# V1.net
KiCad netlist of a schematic drawn in EAGLE
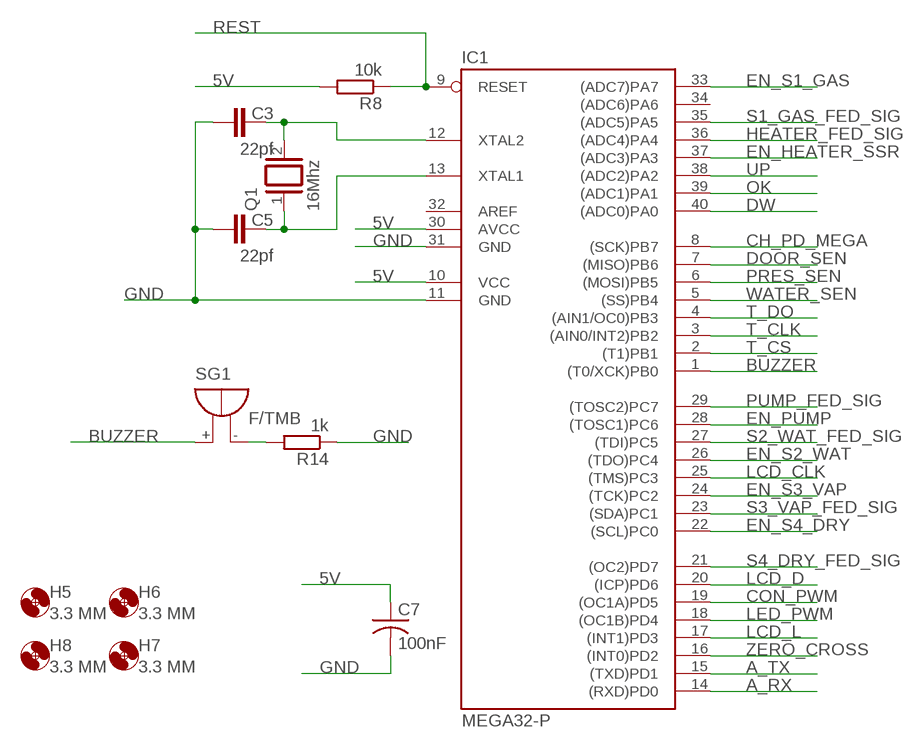
[diagram p0: schematic, sheet 1]
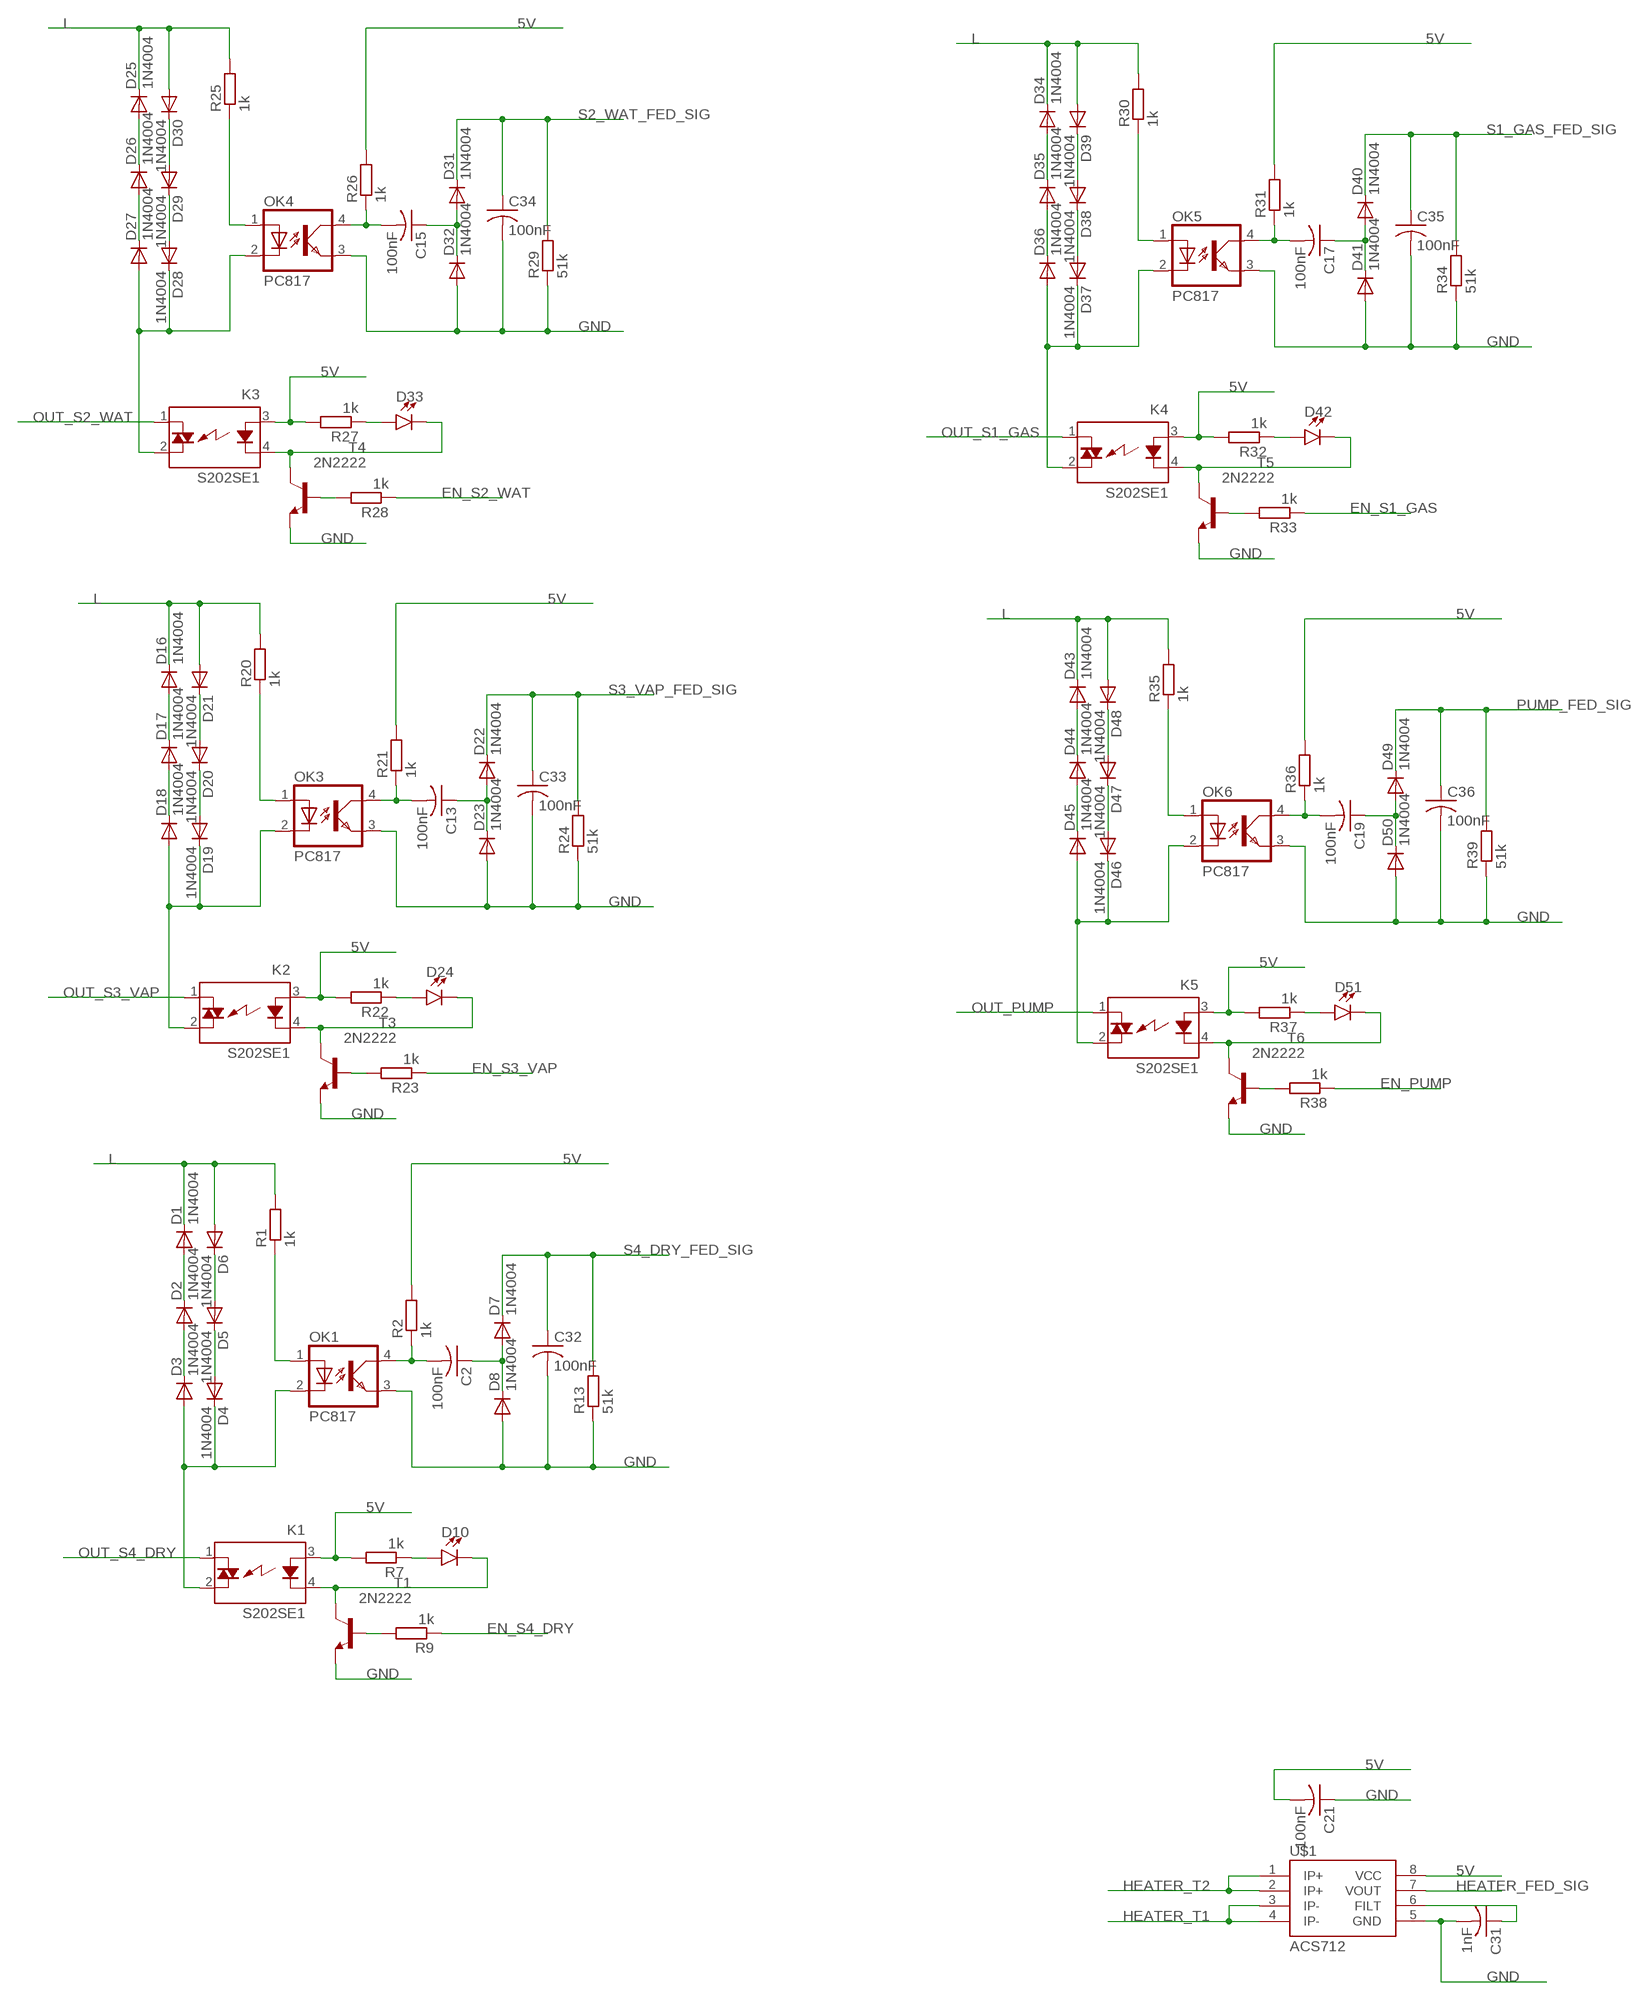
[diagram p1: schematic, sheet 2]
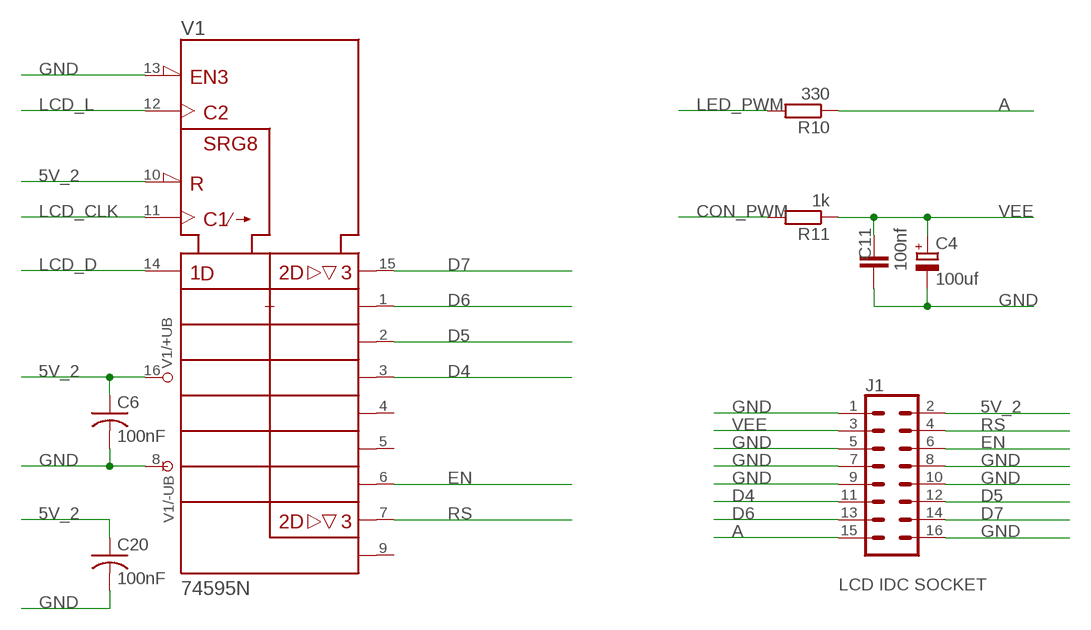
[diagram p2: schematic, sheet 3]
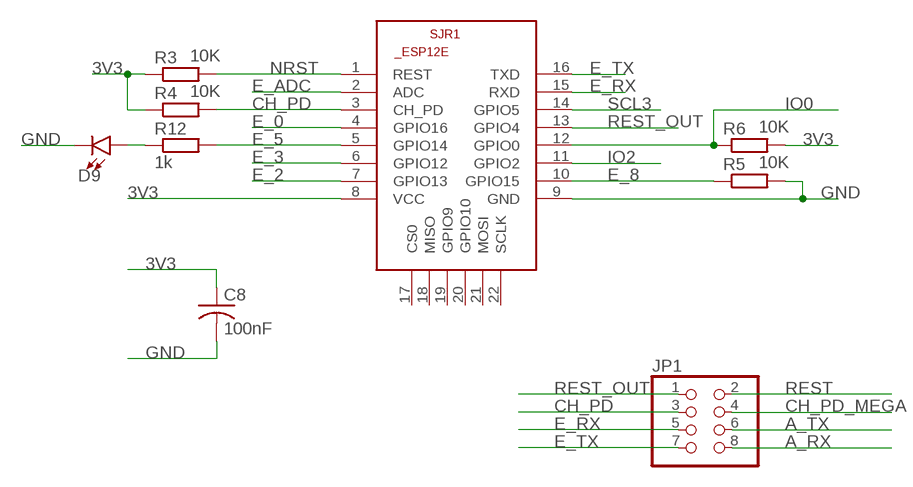
[diagram p3: schematic, sheet 4]
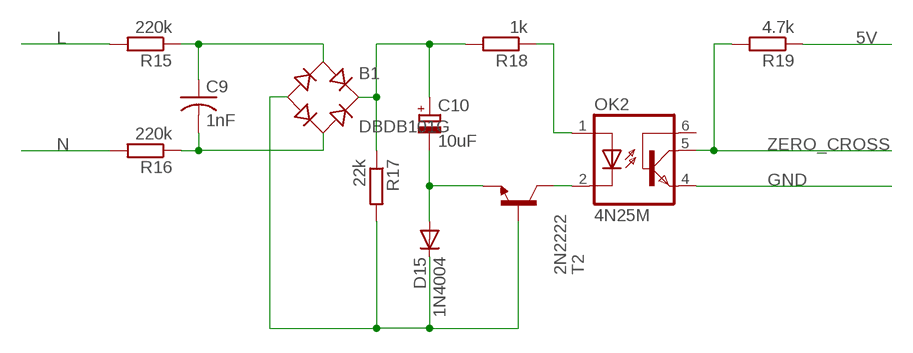
[diagram p4: schematic, sheet 5]
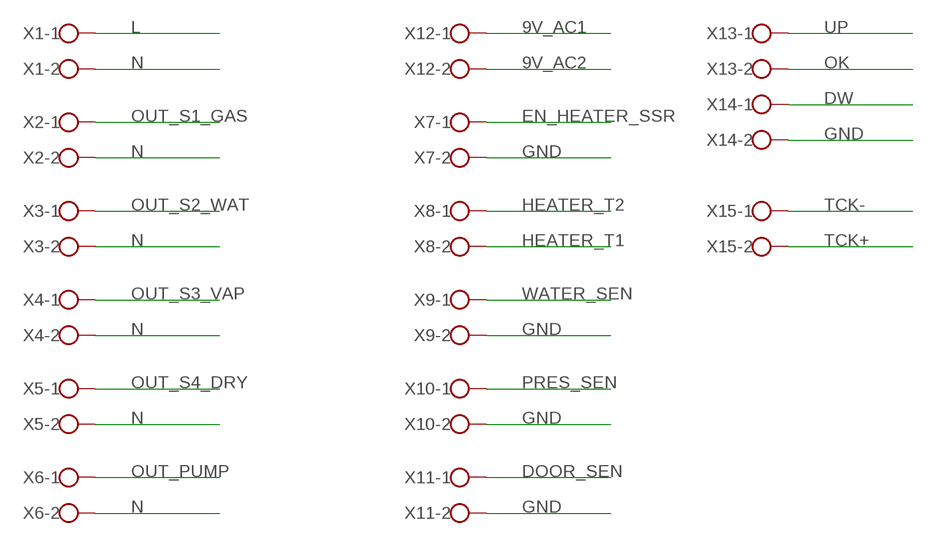
[diagram p5: schematic, sheet 6]
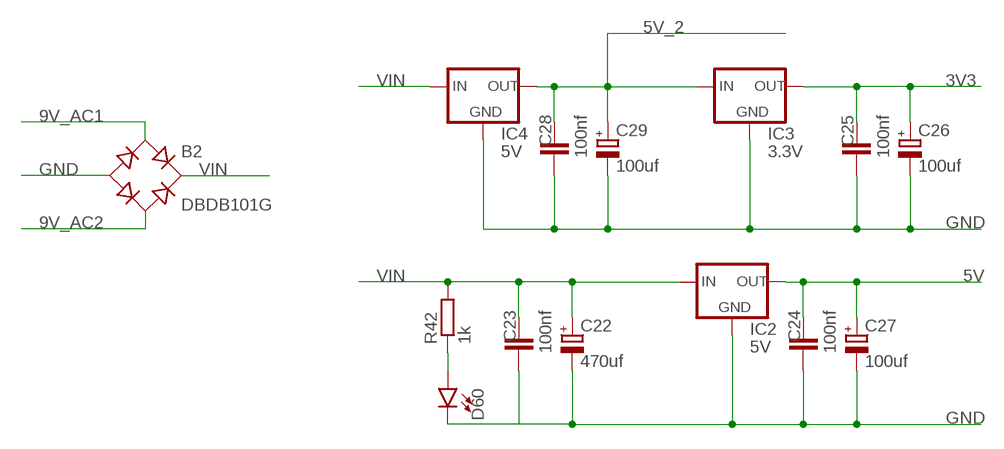
[diagram p6: schematic, sheet 7]
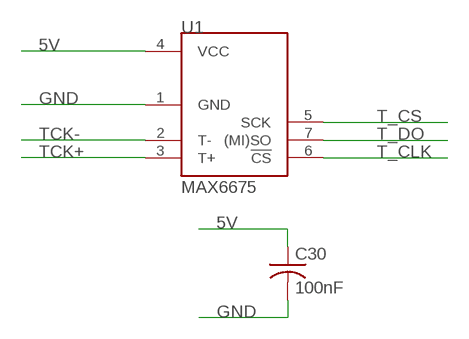
[diagram p7: schematic, sheet 8]

(export (version "E")
  (design (tool "Eeschema 10.0.6"))
  (components
    (comp (ref "C2")
      (value "100nF")
      (footprint "eagle-import:C050-035X075")
      (libsource (lib "eagle-import") (part "C-US050-035X075"))
    )
    (comp (ref "C13")
      (value "100nF")
      (footprint "eagle-import:C050-035X075")
      (libsource (lib "eagle-import") (part "C-US050-035X075"))
    )
    (comp (ref "C15")
      (value "100nF")
      (footprint "eagle-import:C050-035X075")
      (libsource (lib "eagle-import") (part "C-US050-035X075"))
    )
    (comp (ref "C17")
      (value "100nF")
      (footprint "eagle-import:C050-035X075")
      (libsource (lib "eagle-import") (part "C-US050-035X075"))
    )
    (comp (ref "C19")
      (value "100nF")
      (footprint "eagle-import:C050-035X075")
      (libsource (lib "eagle-import") (part "C-US050-035X075"))
    )
    (comp (ref "C21")
      (value "100nF")
      (footprint "eagle-import:C050-035X075")
      (libsource (lib "eagle-import") (part "C-US050-035X075"))
    )
    (comp (ref "C31")
      (value "1nF")
      (footprint "eagle-import:C050-035X075")
      (libsource (lib "eagle-import") (part "C-US050-035X075"))
    )
    (comp (ref "C32")
      (value "100nF")
      (footprint "eagle-import:C050-035X075")
      (libsource (lib "eagle-import") (part "C-US050-035X075"))
    )
    (comp (ref "C33")
      (value "100nF")
      (footprint "eagle-import:C050-035X075")
      (libsource (lib "eagle-import") (part "C-US050-035X075"))
    )
    (comp (ref "C34")
      (value "100nF")
      (footprint "eagle-import:C050-035X075")
      (libsource (lib "eagle-import") (part "C-US050-035X075"))
    )
    (comp (ref "C35")
      (value "100nF")
      (footprint "eagle-import:C050-035X075")
      (libsource (lib "eagle-import") (part "C-US050-035X075"))
    )
    (comp (ref "C36")
      (value "100nF")
      (footprint "eagle-import:C050-035X075")
      (libsource (lib "eagle-import") (part "C-US050-035X075"))
    )
    (comp (ref "D1")
      (value "1N4004")
      (footprint "eagle-import:DO41-10")
      (libsource (lib "eagle-import") (part "1N4004"))
    )
    (comp (ref "D2")
      (value "1N4004")
      (footprint "eagle-import:DO41-10")
      (libsource (lib "eagle-import") (part "1N4004"))
    )
    (comp (ref "D3")
      (value "1N4004")
      (footprint "eagle-import:DO41-10")
      (libsource (lib "eagle-import") (part "1N4004"))
    )
    (comp (ref "D4")
      (value "1N4004")
      (footprint "eagle-import:DO41-10")
      (libsource (lib "eagle-import") (part "1N4004"))
    )
    (comp (ref "D5")
      (value "1N4004")
      (footprint "eagle-import:DO41-10")
      (libsource (lib "eagle-import") (part "1N4004"))
    )
    (comp (ref "D6")
      (value "1N4004")
      (footprint "eagle-import:DO41-10")
      (libsource (lib "eagle-import") (part "1N4004"))
    )
    (comp (ref "D7")
      (value "1N4004")
      (footprint "eagle-import:DO41-10")
      (libsource (lib "eagle-import") (part "1N4004"))
    )
    (comp (ref "D8")
      (value "1N4004")
      (footprint "eagle-import:DO41-10")
      (libsource (lib "eagle-import") (part "1N4004"))
    )
    (comp (ref "D10")
      (value "LED5MM")
      (footprint "eagle-import:LED_5MM")
      (libsource (lib "eagle-import") (part "LED5MM"))
    )
    (comp (ref "D16")
      (value "1N4004")
      (footprint "eagle-import:DO41-10")
      (libsource (lib "eagle-import") (part "1N4004"))
    )
    (comp (ref "D17")
      (value "1N4004")
      (footprint "eagle-import:DO41-10")
      (libsource (lib "eagle-import") (part "1N4004"))
    )
    (comp (ref "D18")
      (value "1N4004")
      (footprint "eagle-import:DO41-10")
      (libsource (lib "eagle-import") (part "1N4004"))
    )
    (comp (ref "D19")
      (value "1N4004")
      (footprint "eagle-import:DO41-10")
      (libsource (lib "eagle-import") (part "1N4004"))
    )
    (comp (ref "D20")
      (value "1N4004")
      (footprint "eagle-import:DO41-10")
      (libsource (lib "eagle-import") (part "1N4004"))
    )
    (comp (ref "D21")
      (value "1N4004")
      (footprint "eagle-import:DO41-10")
      (libsource (lib "eagle-import") (part "1N4004"))
    )
    (comp (ref "D22")
      (value "1N4004")
      (footprint "eagle-import:DO41-10")
      (libsource (lib "eagle-import") (part "1N4004"))
    )
    (comp (ref "D23")
      (value "1N4004")
      (footprint "eagle-import:DO41-10")
      (libsource (lib "eagle-import") (part "1N4004"))
    )
    (comp (ref "D24")
      (value "LED5MM")
      (footprint "eagle-import:LED_5MM")
      (libsource (lib "eagle-import") (part "LED5MM"))
    )
    (comp (ref "D25")
      (value "1N4004")
      (footprint "eagle-import:DO41-10")
      (libsource (lib "eagle-import") (part "1N4004"))
    )
    (comp (ref "D26")
      (value "1N4004")
      (footprint "eagle-import:DO41-10")
      (libsource (lib "eagle-import") (part "1N4004"))
    )
    (comp (ref "D27")
      (value "1N4004")
      (footprint "eagle-import:DO41-10")
      (libsource (lib "eagle-import") (part "1N4004"))
    )
    (comp (ref "D28")
      (value "1N4004")
      (footprint "eagle-import:DO41-10")
      (libsource (lib "eagle-import") (part "1N4004"))
    )
    (comp (ref "D29")
      (value "1N4004")
      (footprint "eagle-import:DO41-10")
      (libsource (lib "eagle-import") (part "1N4004"))
    )
    (comp (ref "D30")
      (value "1N4004")
      (footprint "eagle-import:DO41-10")
      (libsource (lib "eagle-import") (part "1N4004"))
    )
    (comp (ref "D31")
      (value "1N4004")
      (footprint "eagle-import:DO41-10")
      (libsource (lib "eagle-import") (part "1N4004"))
    )
    (comp (ref "D32")
      (value "1N4004")
      (footprint "eagle-import:DO41-10")
      (libsource (lib "eagle-import") (part "1N4004"))
    )
    (comp (ref "D33")
      (value "LED5MM")
      (footprint "eagle-import:LED_5MM")
      (libsource (lib "eagle-import") (part "LED5MM"))
    )
    (comp (ref "D34")
      (value "1N4004")
      (footprint "eagle-import:DO41-10")
      (libsource (lib "eagle-import") (part "1N4004"))
    )
    (comp (ref "D35")
      (value "1N4004")
      (footprint "eagle-import:DO41-10")
      (libsource (lib "eagle-import") (part "1N4004"))
    )
    (comp (ref "D36")
      (value "1N4004")
      (footprint "eagle-import:DO41-10")
      (libsource (lib "eagle-import") (part "1N4004"))
    )
    (comp (ref "D37")
      (value "1N4004")
      (footprint "eagle-import:DO41-10")
      (libsource (lib "eagle-import") (part "1N4004"))
    )
    (comp (ref "D38")
      (value "1N4004")
      (footprint "eagle-import:DO41-10")
      (libsource (lib "eagle-import") (part "1N4004"))
    )
    (comp (ref "D39")
      (value "1N4004")
      (footprint "eagle-import:DO41-10")
      (libsource (lib "eagle-import") (part "1N4004"))
    )
    (comp (ref "D40")
      (value "1N4004")
      (footprint "eagle-import:DO41-10")
      (libsource (lib "eagle-import") (part "1N4004"))
    )
    (comp (ref "D41")
      (value "1N4004")
      (footprint "eagle-import:DO41-10")
      (libsource (lib "eagle-import") (part "1N4004"))
    )
    (comp (ref "D42")
      (value "LED5MM")
      (footprint "eagle-import:LED_5MM")
      (libsource (lib "eagle-import") (part "LED5MM"))
    )
    (comp (ref "D43")
      (value "1N4004")
      (footprint "eagle-import:DO41-10")
      (libsource (lib "eagle-import") (part "1N4004"))
    )
    (comp (ref "D44")
      (value "1N4004")
      (footprint "eagle-import:DO41-10")
      (libsource (lib "eagle-import") (part "1N4004"))
    )
    (comp (ref "D45")
      (value "1N4004")
      (footprint "eagle-import:DO41-10")
      (libsource (lib "eagle-import") (part "1N4004"))
    )
    (comp (ref "D46")
      (value "1N4004")
      (footprint "eagle-import:DO41-10")
      (libsource (lib "eagle-import") (part "1N4004"))
    )
    (comp (ref "D47")
      (value "1N4004")
      (footprint "eagle-import:DO41-10")
      (libsource (lib "eagle-import") (part "1N4004"))
    )
    (comp (ref "D48")
      (value "1N4004")
      (footprint "eagle-import:DO41-10")
      (libsource (lib "eagle-import") (part "1N4004"))
    )
    (comp (ref "D49")
      (value "1N4004")
      (footprint "eagle-import:DO41-10")
      (libsource (lib "eagle-import") (part "1N4004"))
    )
    (comp (ref "D50")
      (value "1N4004")
      (footprint "eagle-import:DO41-10")
      (libsource (lib "eagle-import") (part "1N4004"))
    )
    (comp (ref "D51")
      (value "LED5MM")
      (footprint "eagle-import:LED_5MM")
      (libsource (lib "eagle-import") (part "LED5MM"))
    )
    (comp (ref "K1")
      (value "S202SE1")
      (footprint "eagle-import:S2XXEX")
      (libsource (lib "eagle-import") (part "S202SE1"))
    )
    (comp (ref "K2")
      (value "S202SE1")
      (footprint "eagle-import:S2XXEX")
      (libsource (lib "eagle-import") (part "S202SE1"))
    )
    (comp (ref "K3")
      (value "S202SE1")
      (footprint "eagle-import:S2XXEX")
      (libsource (lib "eagle-import") (part "S202SE1"))
    )
    (comp (ref "K4")
      (value "S202SE1")
      (footprint "eagle-import:S2XXEX")
      (libsource (lib "eagle-import") (part "S202SE1"))
    )
    (comp (ref "K5")
      (value "S202SE1")
      (footprint "eagle-import:S2XXEX")
      (libsource (lib "eagle-import") (part "S202SE1"))
    )
    (comp (ref "OK1")
      (value "PC817")
      (footprint "eagle-import:DIL04")
      (libsource (lib "eagle-import") (part "PC817"))
    )
    (comp (ref "OK3")
      (value "PC817")
      (footprint "eagle-import:DIL04")
      (libsource (lib "eagle-import") (part "PC817"))
    )
    (comp (ref "OK4")
      (value "PC817")
      (footprint "eagle-import:DIL04")
      (libsource (lib "eagle-import") (part "PC817"))
    )
    (comp (ref "OK5")
      (value "PC817")
      (footprint "eagle-import:DIL04")
      (libsource (lib "eagle-import") (part "PC817"))
    )
    (comp (ref "OK6")
      (value "PC817")
      (footprint "eagle-import:DIL04")
      (libsource (lib "eagle-import") (part "PC817"))
    )
    (comp (ref "R1")
      (value "1k")
      (footprint "eagle-import:0207_10")
      (libsource (lib "eagle-import") (part "R-EU_0207/10"))
    )
    (comp (ref "R2")
      (value "1k")
      (footprint "eagle-import:0207_10")
      (libsource (lib "eagle-import") (part "R-EU_0207/10"))
    )
    (comp (ref "R7")
      (value "1k")
      (footprint "eagle-import:0207_10")
      (libsource (lib "eagle-import") (part "R-EU_0207/10"))
    )
    (comp (ref "R9")
      (value "1k")
      (footprint "eagle-import:0207_10")
      (libsource (lib "eagle-import") (part "R-EU_0207/10"))
    )
    (comp (ref "R13")
      (value "51k")
      (footprint "eagle-import:0207_10")
      (libsource (lib "eagle-import") (part "R-EU_0207/10"))
    )
    (comp (ref "R20")
      (value "1k")
      (footprint "eagle-import:0207_10")
      (libsource (lib "eagle-import") (part "R-EU_0207/10"))
    )
    (comp (ref "R21")
      (value "1k")
      (footprint "eagle-import:0207_10")
      (libsource (lib "eagle-import") (part "R-EU_0207/10"))
    )
    (comp (ref "R22")
      (value "1k")
      (footprint "eagle-import:0207_10")
      (libsource (lib "eagle-import") (part "R-EU_0207/10"))
    )
    (comp (ref "R23")
      (value "1k")
      (footprint "eagle-import:0207_10")
      (libsource (lib "eagle-import") (part "R-EU_0207/10"))
    )
    (comp (ref "R24")
      (value "51k")
      (footprint "eagle-import:0207_10")
      (libsource (lib "eagle-import") (part "R-EU_0207/10"))
    )
    (comp (ref "R25")
      (value "1k")
      (footprint "eagle-import:0207_10")
      (libsource (lib "eagle-import") (part "R-EU_0207/10"))
    )
    (comp (ref "R26")
      (value "1k")
      (footprint "eagle-import:0207_10")
      (libsource (lib "eagle-import") (part "R-EU_0207/10"))
    )
    (comp (ref "R27")
      (value "1k")
      (footprint "eagle-import:0207_10")
      (libsource (lib "eagle-import") (part "R-EU_0207/10"))
    )
    (comp (ref "R28")
      (value "1k")
      (footprint "eagle-import:0207_10")
      (libsource (lib "eagle-import") (part "R-EU_0207/10"))
    )
    (comp (ref "R29")
      (value "51k")
      (footprint "eagle-import:0207_10")
      (libsource (lib "eagle-import") (part "R-EU_0207/10"))
    )
    (comp (ref "R30")
      (value "1k")
      (footprint "eagle-import:0207_10")
      (libsource (lib "eagle-import") (part "R-EU_0207/10"))
    )
    (comp (ref "R31")
      (value "1k")
      (footprint "eagle-import:0207_10")
      (libsource (lib "eagle-import") (part "R-EU_0207/10"))
    )
    (comp (ref "R32")
      (value "1k")
      (footprint "eagle-import:0207_10")
      (libsource (lib "eagle-import") (part "R-EU_0207/10"))
    )
    (comp (ref "R33")
      (value "1k")
      (footprint "eagle-import:0207_10")
      (libsource (lib "eagle-import") (part "R-EU_0207/10"))
    )
    (comp (ref "R34")
      (value "51k")
      (footprint "eagle-import:0207_10")
      (libsource (lib "eagle-import") (part "R-EU_0207/10"))
    )
    (comp (ref "R35")
      (value "1k")
      (footprint "eagle-import:0207_10")
      (libsource (lib "eagle-import") (part "R-EU_0207/10"))
    )
    (comp (ref "R36")
      (value "1k")
      (footprint "eagle-import:0207_10")
      (libsource (lib "eagle-import") (part "R-EU_0207/10"))
    )
    (comp (ref "R37")
      (value "1k")
      (footprint "eagle-import:0207_10")
      (libsource (lib "eagle-import") (part "R-EU_0207/10"))
    )
    (comp (ref "R38")
      (value "1k")
      (footprint "eagle-import:0207_10")
      (libsource (lib "eagle-import") (part "R-EU_0207/10"))
    )
    (comp (ref "R39")
      (value "51k")
      (footprint "eagle-import:0207_10")
      (libsource (lib "eagle-import") (part "R-EU_0207/10"))
    )
    (comp (ref "T1")
      (value "2N2222")
      (footprint "eagle-import:TO92-EBC-OVAL")
      (libsource (lib "eagle-import") (part "2N2222"))
    )
    (comp (ref "T3")
      (value "2N2222")
      (footprint "eagle-import:TO92-EBC-OVAL")
      (libsource (lib "eagle-import") (part "2N2222"))
    )
    (comp (ref "T4")
      (value "2N2222")
      (footprint "eagle-import:TO92-EBC-OVAL")
      (libsource (lib "eagle-import") (part "2N2222"))
    )
    (comp (ref "T5")
      (value "2N2222")
      (footprint "eagle-import:TO92-EBC-OVAL")
      (libsource (lib "eagle-import") (part "2N2222"))
    )
    (comp (ref "T6")
      (value "2N2222")
      (footprint "eagle-import:TO92-EBC-OVAL")
      (libsource (lib "eagle-import") (part "2N2222"))
    )
    (comp (ref "U$1")
      (value "ACS712")
      (footprint "eagle-import:SO08")
      (libsource (lib "eagle-import") (part "ACS712"))
    )
    (comp (ref "X1")
      (value "W237-102")
      (footprint "eagle-import:W237-102")
      (fields (field (name "MPN") "237-102"))
      (libsource (lib "eagle-import") (part "W237-102"))
    )
    (comp (ref "X2")
      (value "W237-102")
      (footprint "eagle-import:W237-102")
      (fields (field (name "MPN") "237-102"))
      (libsource (lib "eagle-import") (part "W237-102"))
    )
    (comp (ref "X3")
      (value "W237-102")
      (footprint "eagle-import:W237-102")
      (fields (field (name "MPN") "237-102"))
      (libsource (lib "eagle-import") (part "W237-102"))
    )
    (comp (ref "X4")
      (value "W237-102")
      (footprint "eagle-import:W237-102")
      (fields (field (name "MPN") "237-102"))
      (libsource (lib "eagle-import") (part "W237-102"))
    )
    (comp (ref "X5")
      (value "W237-102")
      (footprint "eagle-import:W237-102")
      (fields (field (name "MPN") "237-102"))
      (libsource (lib "eagle-import") (part "W237-102"))
    )
    (comp (ref "X6")
      (value "W237-102")
      (footprint "eagle-import:W237-102")
      (fields (field (name "MPN") "237-102"))
      (libsource (lib "eagle-import") (part "W237-102"))
    )
    (comp (ref "X7")
      (value "W237-102")
      (footprint "eagle-import:W237-102")
      (fields (field (name "MPN") "237-102"))
      (libsource (lib "eagle-import") (part "W237-102"))
    )
    (comp (ref "X8")
      (value "W237-102")
      (footprint "eagle-import:W237-102")
      (fields (field (name "MPN") "237-102"))
      (libsource (lib "eagle-import") (part "W237-102"))
    )
    (comp (ref "X9")
      (value "W237-102")
      (footprint "eagle-import:W237-102")
      (fields (field (name "MPN") "237-102"))
      (libsource (lib "eagle-import") (part "W237-102"))
    )
    (comp (ref "X10")
      (value "W237-102")
      (footprint "eagle-import:W237-102")
      (fields (field (name "MPN") "237-102"))
      (libsource (lib "eagle-import") (part "W237-102"))
    )
    (comp (ref "X11")
      (value "W237-102")
      (footprint "eagle-import:W237-102")
      (fields (field (name "MPN") "237-102"))
      (libsource (lib "eagle-import") (part "W237-102"))
    )
    (comp (ref "X12")
      (value "W237-102")
      (footprint "eagle-import:W237-102")
      (fields (field (name "MPN") "237-102"))
      (libsource (lib "eagle-import") (part "W237-102"))
    )
    (comp (ref "X13")
      (value "W237-102")
      (footprint "eagle-import:W237-102")
      (fields (field (name "MPN") "237-102"))
      (libsource (lib "eagle-import") (part "W237-102"))
    )
    (comp (ref "X14")
      (value "W237-102")
      (footprint "eagle-import:W237-102")
      (fields (field (name "MPN") "237-102"))
      (libsource (lib "eagle-import") (part "W237-102"))
    )
    (comp (ref "X15")
      (value "W237-102")
      (footprint "eagle-import:W237-102")
      (fields (field (name "MPN") "237-102"))
      (libsource (lib "eagle-import") (part "W237-102"))
    )
    (comp (ref "C3")
      (value "22pf")
      (footprint "eagle-import:C050-030X075")
      (libsource (lib "eagle-import") (part "C-EU050-030X075"))
    )
    (comp (ref "C5")
      (value "22pf")
      (footprint "eagle-import:C050-030X075")
      (libsource (lib "eagle-import") (part "C-EU050-030X075"))
    )
    (comp (ref "C7")
      (value "100nF")
      (footprint "eagle-import:C050-035X075")
      (libsource (lib "eagle-import") (part "C-US050-035X075"))
    )
    (comp (ref "H5")
      (value "3.3 MM")
      (footprint "eagle-import:3,3")
      (libsource (lib "eagle-import") (part "MOUNT-HOLE3.3"))
    )
    (comp (ref "H6")
      (value "3.3 MM")
      (footprint "eagle-import:3,3")
      (libsource (lib "eagle-import") (part "MOUNT-HOLE3.3"))
    )
    (comp (ref "H7")
      (value "3.3 MM")
      (footprint "eagle-import:3,3")
      (libsource (lib "eagle-import") (part "MOUNT-HOLE3.3"))
    )
    (comp (ref "H8")
      (value "3.3 MM")
      (footprint "eagle-import:3,3")
      (libsource (lib "eagle-import") (part "MOUNT-HOLE3.3"))
    )
    (comp (ref "IC1")
      (value "MEGA32-P")
      (footprint "eagle-import:DIL40")
      (fields (field (name "MPN") "ATMEGA32-16PU"))
      (libsource (lib "eagle-import") (part "MEGA32-P"))
    )
    (comp (ref "Q1")
      (value "16Mhz")
      (footprint "eagle-import:QS")
      (libsource (lib "eagle-import") (part "XTAL/S"))
    )
    (comp (ref "R8")
      (value "10k")
      (footprint "eagle-import:0207_10")
      (libsource (lib "eagle-import") (part "R-EU_0207/10"))
    )
    (comp (ref "R14")
      (value "1k")
      (footprint "eagle-import:0207_10")
      (libsource (lib "eagle-import") (part "R-EU_0207/10"))
    )
    (comp (ref "SG1")
      (value "F/TMB")
      (footprint "eagle-import:F_TMB")
      (libsource (lib "eagle-import") (part "F/TMB"))
    )
    (comp (ref "C4")
      (value "100uf")
      (footprint "eagle-import:E3,5-8")
      (libsource (lib "eagle-import") (part "CPOL-EUE3.5-8"))
    )
    (comp (ref "C6")
      (value "100nF")
      (footprint "eagle-import:C050-035X075")
      (libsource (lib "eagle-import") (part "C-US050-035X075"))
    )
    (comp (ref "C11")
      (value "100nf")
      (footprint "eagle-import:C050-030X075")
      (libsource (lib "eagle-import") (part "C-EU050-030X075"))
    )
    (comp (ref "C20")
      (value "100nF")
      (footprint "eagle-import:C050-035X075")
      (libsource (lib "eagle-import") (part "C-US050-035X075"))
    )
    (comp (ref "J1")
      (value "CONN_08X2")
      (footprint "eagle-import:2X8")
      (libsource (lib "eagle-import") (part "CONN_08X2"))
    )
    (comp (ref "R10")
      (value "330")
      (footprint "eagle-import:0207_10")
      (libsource (lib "eagle-import") (part "R-EU_0207/10"))
    )
    (comp (ref "R11")
      (value "1k")
      (footprint "eagle-import:0207_10")
      (libsource (lib "eagle-import") (part "R-EU_0207/10"))
    )
    (comp (ref "V1")
      (value "74595N")
      (footprint "eagle-import:DIL16")
      (libsource (lib "eagle-import") (part "74595N"))
    )
    (comp (ref "B2")
      (value "DBDB101G")
      (footprint "eagle-import:DB")
      (libsource (lib "eagle-import") (part "DB?GDB101"))
    )
    (comp (ref "C22")
      (value "470uf")
      (footprint "eagle-import:E3,5-8")
      (libsource (lib "eagle-import") (part "CPOL-EUE3.5-8"))
    )
    (comp (ref "C23")
      (value "100nf")
      (footprint "eagle-import:C050-030X075")
      (libsource (lib "eagle-import") (part "C-EU050-030X075"))
    )
    (comp (ref "C24")
      (value "100nf")
      (footprint "eagle-import:C050-030X075")
      (libsource (lib "eagle-import") (part "C-EU050-030X075"))
    )
    (comp (ref "C25")
      (value "100nf")
      (footprint "eagle-import:C050-030X075")
      (libsource (lib "eagle-import") (part "C-EU050-030X075"))
    )
    (comp (ref "C26")
      (value "100uf")
      (footprint "eagle-import:E3,5-8")
      (libsource (lib "eagle-import") (part "CPOL-EUE3.5-8"))
    )
    (comp (ref "C27")
      (value "100uf")
      (footprint "eagle-import:E3,5-8")
      (libsource (lib "eagle-import") (part "CPOL-EUE3.5-8"))
    )
    (comp (ref "C28")
      (value "100nf")
      (footprint "eagle-import:C050-030X075")
      (libsource (lib "eagle-import") (part "C-EU050-030X075"))
    )
    (comp (ref "C29")
      (value "100uf")
      (footprint "eagle-import:E3,5-8")
      (libsource (lib "eagle-import") (part "CPOL-EUE3.5-8"))
    )
    (comp (ref "D60")
      (value "LED5MM")
      (footprint "eagle-import:LED_5MM")
      (libsource (lib "eagle-import") (part "LED5MM"))
    )
    (comp (ref "IC2")
      (value "5V")
      (footprint "eagle-import:78XXL")
      (libsource (lib "eagle-import") (part "V_REG_78XXSIDE"))
    )
    (comp (ref "IC3")
      (value "3.3V")
      (footprint "eagle-import:78XXL")
      (libsource (lib "eagle-import") (part "V_REG_78XXSIDE"))
    )
    (comp (ref "IC4")
      (value "5V")
      (footprint "eagle-import:78XXL")
      (libsource (lib "eagle-import") (part "V_REG_78XXSIDE"))
    )
    (comp (ref "R42")
      (value "1k")
      (footprint "eagle-import:0207_10")
      (libsource (lib "eagle-import") (part "R-EU_0207/10"))
    )
    (comp (ref "C8")
      (value "100nF")
      (footprint "eagle-import:C050-035X075")
      (libsource (lib "eagle-import") (part "C-US050-035X075"))
    )
    (comp (ref "D9")
      (value "LED5MM")
      (footprint "eagle-import:LED_5MM")
      (libsource (lib "eagle-import") (part "LED5MM"))
    )
    (comp (ref "JP1")
      (value "PINHD-2X4")
      (footprint "eagle-import:2X04")
      (libsource (lib "eagle-import") (part "PINHD-2X4"))
    )
    (comp (ref "R3")
      (value "10K")
      (footprint "eagle-import:0207_10")
      (libsource (lib "eagle-import") (part "rcl_334_R-EU_0207/10"))
    )
    (comp (ref "R4")
      (value "10K")
      (footprint "eagle-import:0207_10")
      (libsource (lib "eagle-import") (part "rcl_334_R-EU_0207/10"))
    )
    (comp (ref "R5")
      (value "10K")
      (footprint "eagle-import:0207_10")
      (libsource (lib "eagle-import") (part "rcl_334_R-EU_0207/10"))
    )
    (comp (ref "R6")
      (value "10K")
      (footprint "eagle-import:0207_10")
      (libsource (lib "eagle-import") (part "rcl_334_R-EU_0207/10"))
    )
    (comp (ref "R12")
      (value "1k")
      (footprint "eagle-import:0207_10")
      (libsource (lib "eagle-import") (part "R-EU_0207/10"))
    )
    (comp (ref "SJR1")
      (value "ESP8266-12EESP12E")
      (footprint "eagle-import:ESP8266-ESP12E")
      (libsource (lib "eagle-import") (part "ESP8266-12EESP12E"))
    )
    (comp (ref "B1")
      (value "DBDB101G")
      (footprint "eagle-import:DB")
      (libsource (lib "eagle-import") (part "DB?GDB101"))
    )
    (comp (ref "C9")
      (value "1nF")
      (footprint "eagle-import:C050-035X075")
      (libsource (lib "eagle-import") (part "C-US050-035X075"))
    )
    (comp (ref "C10")
      (value "10uF")
      (footprint "eagle-import:E2,5-7")
      (libsource (lib "eagle-import") (part "rcl_334_CPOL-EUE2.5-7"))
    )
    (comp (ref "D15")
      (value "1N4004")
      (footprint "eagle-import:DO41-10")
      (libsource (lib "eagle-import") (part "1N4004"))
    )
    (comp (ref "OK2")
      (value "4N25M")
      (footprint "eagle-import:DIL06")
      (fields (field (name "MPN") "4N25-M"))
      (libsource (lib "eagle-import") (part "4N?M25"))
    )
    (comp (ref "R15")
      (value "220k")
      (footprint "eagle-import:0207_10")
      (libsource (lib "eagle-import") (part "R-EU_0207/10"))
    )
    (comp (ref "R16")
      (value "220k")
      (footprint "eagle-import:0207_10")
      (libsource (lib "eagle-import") (part "R-EU_0207/10"))
    )
    (comp (ref "R17")
      (value "22k")
      (footprint "eagle-import:0207_10")
      (libsource (lib "eagle-import") (part "R-EU_0207/10"))
    )
    (comp (ref "R18")
      (value "1k")
      (footprint "eagle-import:0207_10")
      (libsource (lib "eagle-import") (part "R-EU_0207/10"))
    )
    (comp (ref "R19")
      (value "4.7k")
      (footprint "eagle-import:0207_10")
      (libsource (lib "eagle-import") (part "R-EU_0207/10"))
    )
    (comp (ref "T2")
      (value "2N2222")
      (footprint "eagle-import:TO92-EBC-OVAL")
      (libsource (lib "eagle-import") (part "2N2222"))
    )
    (comp (ref "C30")
      (value "100nF")
      (footprint "eagle-import:C050-035X075")
      (libsource (lib "eagle-import") (part "C-US050-035X075"))
    )
    (comp (ref "U1")
      (value "MAX6675")
      (footprint "eagle-import:SOIC8")
      (libsource (lib "eagle-import") (part "MAX6675"))
    )
  )
  (nets
    (net (code "1") (name "3V3") (class "Default")
      (node (ref "C25") (pin "2") (pinfunction "2_2") (pintype "passive"))
      (node (ref "C26") (pin "+") (pinfunction "+_+") (pintype "passive"))
      (node (ref "C8") (pin "1") (pinfunction "1_1") (pintype "passive"))
      (node (ref "IC3") (pin "OUT") (pinfunction "OUT_OUT") (pintype "output"))
      (node (ref "R3") (pin "1") (pinfunction "1_1") (pintype "passive"))
      (node (ref "R4") (pin "1") (pinfunction "1_1") (pintype "passive"))
      (node (ref "R6") (pin "2") (pinfunction "2_2") (pintype "passive"))
      (node (ref "SJR1") (pin "8") (pinfunction "VCC_8") (pintype "bidirectional"))
    )
    (net (code "2") (name "5V") (class "Default")
      (node (ref "C21") (pin "2") (pinfunction "2_2") (pintype "passive"))
      (node (ref "C24") (pin "2") (pinfunction "2_2") (pintype "passive"))
      (node (ref "C27") (pin "+") (pinfunction "+_+") (pintype "passive"))
      (node (ref "C30") (pin "1") (pinfunction "1_1") (pintype "passive"))
      (node (ref "C7") (pin "1") (pinfunction "1_1") (pintype "passive"))
      (node (ref "IC1") (pin "10") (pinfunction "VCC_10") (pintype "power_in"))
      (node (ref "IC1") (pin "30") (pinfunction "AVCC_30") (pintype "power_in"))
      (node (ref "IC2") (pin "OUT") (pinfunction "OUT_OUT") (pintype "output"))
      (node (ref "K1") (pin "3") (pinfunction "A_3") (pintype "passive"))
      (node (ref "K2") (pin "3") (pinfunction "A_3") (pintype "passive"))
      (node (ref "K3") (pin "3") (pinfunction "A_3") (pintype "passive"))
      (node (ref "K4") (pin "3") (pinfunction "A_3") (pintype "passive"))
      (node (ref "K5") (pin "3") (pinfunction "A_3") (pintype "passive"))
      (node (ref "R19") (pin "1") (pinfunction "1_1") (pintype "passive"))
      (node (ref "R2") (pin "2") (pinfunction "2_2") (pintype "passive"))
      (node (ref "R21") (pin "2") (pinfunction "2_2") (pintype "passive"))
      (node (ref "R22") (pin "2") (pinfunction "2_2") (pintype "passive"))
      (node (ref "R26") (pin "2") (pinfunction "2_2") (pintype "passive"))
      (node (ref "R27") (pin "2") (pinfunction "2_2") (pintype "passive"))
      (node (ref "R31") (pin "2") (pinfunction "2_2") (pintype "passive"))
      (node (ref "R32") (pin "2") (pinfunction "2_2") (pintype "passive"))
      (node (ref "R36") (pin "2") (pinfunction "2_2") (pintype "passive"))
      (node (ref "R37") (pin "2") (pinfunction "2_2") (pintype "passive"))
      (node (ref "R7") (pin "2") (pinfunction "2_2") (pintype "passive"))
      (node (ref "R8") (pin "2") (pinfunction "2_2") (pintype "passive"))
      (node (ref "U$1") (pin "8") (pinfunction "VCC_8") (pintype "bidirectional"))
      (node (ref "U1") (pin "4") (pinfunction "VCC_4") (pintype "bidirectional"))
    )
    (net (code "3") (name "5V_2") (class "Default")
      (node (ref "C20") (pin "1") (pinfunction "1_1") (pintype "passive"))
      (node (ref "C28") (pin "2") (pinfunction "2_2") (pintype "passive"))
      (node (ref "C29") (pin "+") (pinfunction "+_+") (pintype "passive"))
      (node (ref "C6") (pin "1") (pinfunction "1_1") (pintype "passive"))
      (node (ref "IC3") (pin "IN") (pinfunction "IN_IN") (pintype "input"))
      (node (ref "IC4") (pin "OUT") (pinfunction "OUT_OUT") (pintype "output"))
      (node (ref "J1") (pin "2") (pinfunction "2_2") (pintype "passive"))
      (node (ref "V1") (pin "10") (pinfunction "~{SRCLR}_10") (pintype "input"))
      (node (ref "V1") (pin "16") (pinfunction "+UB_16") (pintype "power_in"))
    )
    (net (code "4") (name "9V_AC1") (class "Default")
      (node (ref "B2") (pin "AC1") (pinfunction "AC1_AC1") (pintype "passive"))
      (node (ref "X12") (pin "1") (pinfunction "KL_1") (pintype "passive"))
    )
    (net (code "5") (name "9V_AC2") (class "Default")
      (node (ref "B2") (pin "AC2") (pinfunction "AC2_AC2") (pintype "passive"))
      (node (ref "X12") (pin "2") (pinfunction "KL_2") (pintype "passive"))
    )
    (net (code "6") (name "A") (class "Default")
      (node (ref "J1") (pin "15") (pinfunction "15_15") (pintype "passive"))
      (node (ref "R10") (pin "1") (pinfunction "1_1") (pintype "passive"))
    )
    (net (code "7") (name "A_RX") (class "Default")
      (node (ref "IC1") (pin "14") (pinfunction "(RXD)PD0_14") (pintype "bidirectional"))
      (node (ref "JP1") (pin "8") (pinfunction "8_8") (pintype "passive"))
    )
    (net (code "8") (name "A_TX") (class "Default")
      (node (ref "IC1") (pin "15") (pinfunction "(TXD)PD1_15") (pintype "bidirectional"))
      (node (ref "JP1") (pin "6") (pinfunction "6_6") (pintype "passive"))
    )
    (net (code "9") (name "BUZZER") (class "Default")
      (node (ref "IC1") (pin "1") (pinfunction "(T0/XCK)PB0_1") (pintype "bidirectional"))
      (node (ref "SG1") (pin "+") (pinfunction "+_+") (pintype "passive"))
    )
    (net (code "10") (name "CH_PD") (class "Default")
      (node (ref "JP1") (pin "3") (pinfunction "3_3") (pintype "passive"))
      (node (ref "R4") (pin "2") (pinfunction "2_2") (pintype "passive"))
      (node (ref "SJR1") (pin "3") (pinfunction "CH_PD_3") (pintype "bidirectional"))
    )
    (net (code "11") (name "CH_PD_MEGA") (class "Default")
      (node (ref "IC1") (pin "8") (pinfunction "(SCK)PB7_8") (pintype "bidirectional"))
      (node (ref "JP1") (pin "4") (pinfunction "4_4") (pintype "passive"))
    )
    (net (code "12") (name "CON_PWM") (class "Default")
      (node (ref "IC1") (pin "19") (pinfunction "(OC1A)PD5_19") (pintype "bidirectional"))
      (node (ref "R11") (pin "2") (pinfunction "2_2") (pintype "passive"))
    )
    (net (code "13") (name "D4") (class "Default")
      (node (ref "J1") (pin "11") (pinfunction "11_11") (pintype "passive"))
      (node (ref "V1") (pin "3") (pinfunction "QD_3") (pintype "tri_state"))
    )
    (net (code "14") (name "D5") (class "Default")
      (node (ref "J1") (pin "12") (pinfunction "12_12") (pintype "passive"))
      (node (ref "V1") (pin "2") (pinfunction "QC_2") (pintype "tri_state"))
    )
    (net (code "15") (name "D6") (class "Default")
      (node (ref "J1") (pin "13") (pinfunction "13_13") (pintype "passive"))
      (node (ref "V1") (pin "1") (pinfunction "QB_1") (pintype "tri_state"))
    )
    (net (code "16") (name "D7") (class "Default")
      (node (ref "J1") (pin "14") (pinfunction "14_14") (pintype "passive"))
      (node (ref "V1") (pin "15") (pinfunction "QA_15") (pintype "tri_state"))
    )
    (net (code "17") (name "DOOR_SEN") (class "Default")
      (node (ref "IC1") (pin "7") (pinfunction "(MISO)PB6_7") (pintype "bidirectional"))
      (node (ref "X11") (pin "1") (pinfunction "KL_1") (pintype "passive"))
    )
    (net (code "18") (name "DW") (class "Default")
      (node (ref "IC1") (pin "40") (pinfunction "(ADC0)PA0_40") (pintype "bidirectional"))
      (node (ref "X14") (pin "1") (pinfunction "KL_1") (pintype "passive"))
    )
    (net (code "19") (name "EN") (class "Default")
      (node (ref "J1") (pin "6") (pinfunction "6_6") (pintype "passive"))
      (node (ref "V1") (pin "6") (pinfunction "QG_6") (pintype "tri_state"))
    )
    (net (code "20") (name "EN_HEATER_SSR") (class "Default")
      (node (ref "IC1") (pin "37") (pinfunction "(ADC3)PA3_37") (pintype "bidirectional"))
      (node (ref "X7") (pin "1") (pinfunction "KL_1") (pintype "passive"))
    )
    (net (code "21") (name "EN_PUMP") (class "Default")
      (node (ref "IC1") (pin "28") (pinfunction "(TOSC1)PC6_28") (pintype "bidirectional"))
      (node (ref "R38") (pin "1") (pinfunction "1_1") (pintype "passive"))
    )
    (net (code "22") (name "EN_S1_GAS") (class "Default")
      (node (ref "IC1") (pin "33") (pinfunction "(ADC7)PA7_33") (pintype "bidirectional"))
      (node (ref "R33") (pin "1") (pinfunction "1_1") (pintype "passive"))
    )
    (net (code "23") (name "EN_S2_WAT") (class "Default")
      (node (ref "IC1") (pin "26") (pinfunction "(TDO)PC4_26") (pintype "bidirectional"))
      (node (ref "R28") (pin "1") (pinfunction "1_1") (pintype "passive"))
    )
    (net (code "24") (name "EN_S3_VAP") (class "Default")
      (node (ref "IC1") (pin "24") (pinfunction "(TCK)PC2_24") (pintype "bidirectional"))
      (node (ref "R23") (pin "1") (pinfunction "1_1") (pintype "passive"))
    )
    (net (code "25") (name "EN_S4_DRY") (class "Default")
      (node (ref "IC1") (pin "22") (pinfunction "(SCL)PC0_22") (pintype "bidirectional"))
      (node (ref "R9") (pin "1") (pinfunction "1_1") (pintype "passive"))
    )
    (net (code "26") (name "E_0") (class "Default")
      (node (ref "SJR1") (pin "4") (pinfunction "GPIO16_4") (pintype "bidirectional"))
    )
    (net (code "27") (name "E_2") (class "Default")
      (node (ref "SJR1") (pin "7") (pinfunction "GPIO13_7") (pintype "bidirectional"))
    )
    (net (code "28") (name "E_3") (class "Default")
      (node (ref "SJR1") (pin "6") (pinfunction "GPIO12_6") (pintype "bidirectional"))
    )
    (net (code "29") (name "E_5") (class "Default")
      (node (ref "R12") (pin "2") (pinfunction "2_2") (pintype "passive"))
      (node (ref "SJR1") (pin "5") (pinfunction "GPIO14_5") (pintype "bidirectional"))
    )
    (net (code "30") (name "E_8") (class "Default")
      (node (ref "R5") (pin "1") (pinfunction "1_1") (pintype "passive"))
      (node (ref "SJR1") (pin "10") (pinfunction "GPIO15_10") (pintype "bidirectional"))
    )
    (net (code "31") (name "E_ADC") (class "Default")
      (node (ref "SJR1") (pin "2") (pinfunction "ADC_2") (pintype "bidirectional"))
    )
    (net (code "32") (name "E_RX") (class "Default")
      (node (ref "JP1") (pin "5") (pinfunction "5_5") (pintype "passive"))
      (node (ref "SJR1") (pin "15") (pinfunction "RXD_15") (pintype "bidirectional"))
    )
    (net (code "33") (name "E_TX") (class "Default")
      (node (ref "JP1") (pin "7") (pinfunction "7_7") (pintype "passive"))
      (node (ref "SJR1") (pin "16") (pinfunction "TXD_16") (pintype "bidirectional"))
    )
    (net (code "34") (name "GND") (class "Default")
      (node (ref "B2") (pin "-") (pinfunction "-_-") (pintype "passive"))
      (node (ref "C11") (pin "1") (pinfunction "1_1") (pintype "passive"))
      (node (ref "C20") (pin "2") (pinfunction "2_2") (pintype "passive"))
      (node (ref "C21") (pin "1") (pinfunction "1_1") (pintype "passive"))
      (node (ref "C22") (pin "-") (pinfunction "-_-") (pintype "passive"))
      (node (ref "C23") (pin "1") (pinfunction "1_1") (pintype "passive"))
      (node (ref "C24") (pin "1") (pinfunction "1_1") (pintype "passive"))
      (node (ref "C25") (pin "1") (pinfunction "1_1") (pintype "passive"))
      (node (ref "C26") (pin "-") (pinfunction "-_-") (pintype "passive"))
      (node (ref "C27") (pin "-") (pinfunction "-_-") (pintype "passive"))
      (node (ref "C28") (pin "1") (pinfunction "1_1") (pintype "passive"))
      (node (ref "C29") (pin "-") (pinfunction "-_-") (pintype "passive"))
      (node (ref "C3") (pin "1") (pinfunction "1_1") (pintype "passive"))
      (node (ref "C30") (pin "2") (pinfunction "2_2") (pintype "passive"))
      (node (ref "C31") (pin "2") (pinfunction "2_2") (pintype "passive"))
      (node (ref "C32") (pin "2") (pinfunction "2_2") (pintype "passive"))
      (node (ref "C33") (pin "2") (pinfunction "2_2") (pintype "passive"))
      (node (ref "C34") (pin "2") (pinfunction "2_2") (pintype "passive"))
      (node (ref "C35") (pin "2") (pinfunction "2_2") (pintype "passive"))
      (node (ref "C36") (pin "2") (pinfunction "2_2") (pintype "passive"))
      (node (ref "C4") (pin "-") (pinfunction "-_-") (pintype "passive"))
      (node (ref "C5") (pin "1") (pinfunction "1_1") (pintype "passive"))
      (node (ref "C6") (pin "2") (pinfunction "2_2") (pintype "passive"))
      (node (ref "C7") (pin "2") (pinfunction "2_2") (pintype "passive"))
      (node (ref "C8") (pin "2") (pinfunction "2_2") (pintype "passive"))
      (node (ref "D23") (pin "A") (pinfunction "A_A") (pintype "passive"))
      (node (ref "D32") (pin "A") (pinfunction "A_A") (pintype "passive"))
      (node (ref "D41") (pin "A") (pinfunction "A_A") (pintype "passive"))
      (node (ref "D50") (pin "A") (pinfunction "A_A") (pintype "passive"))
      (node (ref "D60") (pin "K") (pinfunction "C_K") (pintype "passive"))
      (node (ref "D8") (pin "A") (pinfunction "A_A") (pintype "passive"))
      (node (ref "D9") (pin "K") (pinfunction "C_K") (pintype "passive"))
      (node (ref "IC1") (pin "11") (pinfunction "GND_11") (pintype "power_in"))
      (node (ref "IC1") (pin "31") (pinfunction "GND_31") (pintype "power_in"))
      (node (ref "IC2") (pin "GND") (pinfunction "GND_GND") (pintype "input"))
      (node (ref "IC3") (pin "GND") (pinfunction "GND_GND") (pintype "input"))
      (node (ref "IC4") (pin "GND") (pinfunction "GND_GND") (pintype "input"))
      (node (ref "J1") (pin "1") (pinfunction "1_1") (pintype "passive"))
      (node (ref "J1") (pin "10") (pinfunction "10_10") (pintype "passive"))
      (node (ref "J1") (pin "16") (pinfunction "16_16") (pintype "passive"))
      (node (ref "J1") (pin "5") (pinfunction "5_5") (pintype "passive"))
      (node (ref "J1") (pin "7") (pinfunction "7_7") (pintype "passive"))
      (node (ref "J1") (pin "8") (pinfunction "8_8") (pintype "passive"))
      (node (ref "J1") (pin "9") (pinfunction "9_9") (pintype "passive"))
      (node (ref "OK1") (pin "3") (pinfunction "EMIT_3") (pintype "passive"))
      (node (ref "OK2") (pin "4") (pinfunction "EMI_4") (pintype "passive"))
      (node (ref "OK3") (pin "3") (pinfunction "EMIT_3") (pintype "passive"))
      (node (ref "OK4") (pin "3") (pinfunction "EMIT_3") (pintype "passive"))
      (node (ref "OK5") (pin "3") (pinfunction "EMIT_3") (pintype "passive"))
      (node (ref "OK6") (pin "3") (pinfunction "EMIT_3") (pintype "passive"))
      (node (ref "R13") (pin "1") (pinfunction "1_1") (pintype "passive"))
      (node (ref "R14") (pin "1") (pinfunction "1_1") (pintype "passive"))
      (node (ref "R24") (pin "1") (pinfunction "1_1") (pintype "passive"))
      (node (ref "R29") (pin "1") (pinfunction "1_1") (pintype "passive"))
      (node (ref "R34") (pin "1") (pinfunction "1_1") (pintype "passive"))
      (node (ref "R39") (pin "1") (pinfunction "1_1") (pintype "passive"))
      (node (ref "R5") (pin "2") (pinfunction "2_2") (pintype "passive"))
      (node (ref "SJR1") (pin "9") (pinfunction "GND_9") (pintype "bidirectional"))
      (node (ref "T1") (pin "E") (pinfunction "E_E") (pintype "passive"))
      (node (ref "T3") (pin "E") (pinfunction "E_E") (pintype "passive"))
      (node (ref "T4") (pin "E") (pinfunction "E_E") (pintype "passive"))
      (node (ref "T5") (pin "E") (pinfunction "E_E") (pintype "passive"))
      (node (ref "T6") (pin "E") (pinfunction "E_E") (pintype "passive"))
      (node (ref "U$1") (pin "5") (pinfunction "GND_5") (pintype "bidirectional"))
      (node (ref "U1") (pin "1") (pinfunction "GND_1") (pintype "bidirectional"))
      (node (ref "V1") (pin "13") (pinfunction "~{G}_13") (pintype "input"))
      (node (ref "V1") (pin "8") (pinfunction "-UB_8") (pintype "power_in"))
      (node (ref "X10") (pin "2") (pinfunction "KL_2") (pintype "passive"))
      (node (ref "X11") (pin "2") (pinfunction "KL_2") (pintype "passive"))
      (node (ref "X14") (pin "2") (pinfunction "KL_2") (pintype "passive"))
      (node (ref "X7") (pin "2") (pinfunction "KL_2") (pintype "passive"))
      (node (ref "X9") (pin "2") (pinfunction "KL_2") (pintype "passive"))
    )
    (net (code "35") (name "HEATER_FED_SIG") (class "Default")
      (node (ref "IC1") (pin "36") (pinfunction "(ADC4)PA4_36") (pintype "bidirectional"))
      (node (ref "U$1") (pin "7") (pinfunction "VOUT_7") (pintype "bidirectional"))
    )
    (net (code "36") (name "HEATER_T1") (class "Default")
      (node (ref "U$1") (pin "3") (pinfunction "IP-_3") (pintype "bidirectional"))
      (node (ref "U$1") (pin "4") (pinfunction "IP-_4") (pintype "bidirectional"))
      (node (ref "X8") (pin "2") (pinfunction "KL_2") (pintype "passive"))
    )
    (net (code "37") (name "HEATER_T2") (class "Default")
      (node (ref "U$1") (pin "1") (pinfunction "IP+_1") (pintype "bidirectional"))
      (node (ref "U$1") (pin "2") (pinfunction "IP+_2") (pintype "bidirectional"))
      (node (ref "X8") (pin "1") (pinfunction "KL_1") (pintype "passive"))
    )
    (net (code "38") (name "IO0") (class "Default")
      (node (ref "R6") (pin "1") (pinfunction "1_1") (pintype "passive"))
      (node (ref "SJR1") (pin "12") (pinfunction "GPIO0_12") (pintype "bidirectional"))
    )
    (net (code "39") (name "IO2") (class "Default")
      (node (ref "SJR1") (pin "11") (pinfunction "GPIO2_11") (pintype "bidirectional"))
    )
    (net (code "40") (name "L") (class "Default")
      (node (ref "D1") (pin "C") (pinfunction "C_C") (pintype "passive"))
      (node (ref "D16") (pin "C") (pinfunction "C_C") (pintype "passive"))
      (node (ref "D21") (pin "A") (pinfunction "A_A") (pintype "passive"))
      (node (ref "D25") (pin "C") (pinfunction "C_C") (pintype "passive"))
      (node (ref "D30") (pin "A") (pinfunction "A_A") (pintype "passive"))
      (node (ref "D34") (pin "C") (pinfunction "C_C") (pintype "passive"))
      (node (ref "D39") (pin "A") (pinfunction "A_A") (pintype "passive"))
      (node (ref "D43") (pin "C") (pinfunction "C_C") (pintype "passive"))
      (node (ref "D48") (pin "A") (pinfunction "A_A") (pintype "passive"))
      (node (ref "D6") (pin "A") (pinfunction "A_A") (pintype "passive"))
      (node (ref "R1") (pin "2") (pinfunction "2_2") (pintype "passive"))
      (node (ref "R15") (pin "2") (pinfunction "2_2") (pintype "passive"))
      (node (ref "R20") (pin "2") (pinfunction "2_2") (pintype "passive"))
      (node (ref "R25") (pin "2") (pinfunction "2_2") (pintype "passive"))
      (node (ref "R30") (pin "2") (pinfunction "2_2") (pintype "passive"))
      (node (ref "R35") (pin "2") (pinfunction "2_2") (pintype "passive"))
      (node (ref "X1") (pin "1") (pinfunction "KL_1") (pintype "passive"))
    )
    (net (code "41") (name "LCD_CLK") (class "Default")
      (node (ref "IC1") (pin "25") (pinfunction "(TMS)PC3_25") (pintype "bidirectional"))
      (node (ref "V1") (pin "11") (pinfunction "SRCK_11") (pintype "input"))
    )
    (net (code "42") (name "LCD_D") (class "Default")
      (node (ref "IC1") (pin "20") (pinfunction "(ICP)PD6_20") (pintype "bidirectional"))
      (node (ref "V1") (pin "14") (pinfunction "SER_14") (pintype "input"))
    )
    (net (code "43") (name "LCD_L") (class "Default")
      (node (ref "IC1") (pin "17") (pinfunction "(INT1)PD3_17") (pintype "bidirectional"))
      (node (ref "V1") (pin "12") (pinfunction "RCK_12") (pintype "input"))
    )
    (net (code "44") (name "LED_PWM") (class "Default")
      (node (ref "IC1") (pin "18") (pinfunction "(OC1B)PD4_18") (pintype "bidirectional"))
      (node (ref "R10") (pin "2") (pinfunction "2_2") (pintype "passive"))
    )
    (net (code "45") (name "N") (class "Default")
      (node (ref "R16") (pin "2") (pinfunction "2_2") (pintype "passive"))
      (node (ref "X1") (pin "2") (pinfunction "KL_2") (pintype "passive"))
      (node (ref "X2") (pin "2") (pinfunction "KL_2") (pintype "passive"))
      (node (ref "X3") (pin "2") (pinfunction "KL_2") (pintype "passive"))
      (node (ref "X4") (pin "2") (pinfunction "KL_2") (pintype "passive"))
      (node (ref "X5") (pin "2") (pinfunction "KL_2") (pintype "passive"))
      (node (ref "X6") (pin "2") (pinfunction "KL_2") (pintype "passive"))
    )
    (net (code "46") (name "NRST") (class "Default")
      (node (ref "R3") (pin "2") (pinfunction "2_2") (pintype "passive"))
      (node (ref "SJR1") (pin "1") (pinfunction "REST_1") (pintype "bidirectional"))
    )
    (net (code "47") (name "Net-(B1-Pad+)") (class "Default")
      (node (ref "B1") (pin "+") (pinfunction "+_+") (pintype "passive"))
      (node (ref "C10") (pin "+") (pinfunction "+_+") (pintype "passive"))
      (node (ref "R17") (pin "1") (pinfunction "1_1") (pintype "passive"))
      (node (ref "R18") (pin "2") (pinfunction "2_2") (pintype "passive"))
    )
    (net (code "48") (name "Net-(B1-Pad-)") (class "Default")
      (node (ref "B1") (pin "-") (pinfunction "-_-") (pintype "passive"))
      (node (ref "D15") (pin "C") (pinfunction "C_C") (pintype "passive"))
      (node (ref "R17") (pin "2") (pinfunction "2_2") (pintype "passive"))
      (node (ref "T2") (pin "B") (pinfunction "B_B") (pintype "passive"))
    )
    (net (code "49") (name "Net-(B1-PadAC1)") (class "Default")
      (node (ref "B1") (pin "AC1") (pinfunction "AC1_AC1") (pintype "passive"))
      (node (ref "C9") (pin "1") (pinfunction "1_1") (pintype "passive"))
      (node (ref "R15") (pin "1") (pinfunction "1_1") (pintype "passive"))
    )
    (net (code "50") (name "Net-(B1-PadAC2)") (class "Default")
      (node (ref "B1") (pin "AC2") (pinfunction "AC2_AC2") (pintype "passive"))
      (node (ref "C9") (pin "2") (pinfunction "2_2") (pintype "passive"))
      (node (ref "R16") (pin "1") (pinfunction "1_1") (pintype "passive"))
    )
    (net (code "51") (name "Net-(C2-Pad1)") (class "Default")
      (node (ref "C2") (pin "1") (pinfunction "1_1") (pintype "passive"))
      (node (ref "D7") (pin "A") (pinfunction "A_A") (pintype "passive"))
      (node (ref "D8") (pin "C") (pinfunction "C_C") (pintype "passive"))
    )
    (net (code "52") (name "Net-(C10-Pad-)") (class "Default")
      (node (ref "C10") (pin "-") (pinfunction "-_-") (pintype "passive"))
      (node (ref "D15") (pin "A") (pinfunction "A_A") (pintype "passive"))
      (node (ref "T2") (pin "E") (pinfunction "E_E") (pintype "passive"))
    )
    (net (code "53") (name "Net-(C13-Pad1)") (class "Default")
      (node (ref "C13") (pin "1") (pinfunction "1_1") (pintype "passive"))
      (node (ref "D22") (pin "A") (pinfunction "A_A") (pintype "passive"))
      (node (ref "D23") (pin "C") (pinfunction "C_C") (pintype "passive"))
    )
    (net (code "54") (name "Net-(C15-Pad1)") (class "Default")
      (node (ref "C15") (pin "1") (pinfunction "1_1") (pintype "passive"))
      (node (ref "D31") (pin "A") (pinfunction "A_A") (pintype "passive"))
      (node (ref "D32") (pin "C") (pinfunction "C_C") (pintype "passive"))
    )
    (net (code "55") (name "Net-(C17-Pad1)") (class "Default")
      (node (ref "C17") (pin "1") (pinfunction "1_1") (pintype "passive"))
      (node (ref "D40") (pin "A") (pinfunction "A_A") (pintype "passive"))
      (node (ref "D41") (pin "C") (pinfunction "C_C") (pintype "passive"))
    )
    (net (code "56") (name "Net-(C19-Pad1)") (class "Default")
      (node (ref "C19") (pin "1") (pinfunction "1_1") (pintype "passive"))
      (node (ref "D49") (pin "A") (pinfunction "A_A") (pintype "passive"))
      (node (ref "D50") (pin "C") (pinfunction "C_C") (pintype "passive"))
    )
    (net (code "57") (name "Net-(D1-PadA)") (class "Default")
      (node (ref "D1") (pin "A") (pinfunction "A_A") (pintype "passive"))
      (node (ref "D2") (pin "C") (pinfunction "C_C") (pintype "passive"))
    )
    (net (code "58") (name "Net-(D2-PadA)") (class "Default")
      (node (ref "D2") (pin "A") (pinfunction "A_A") (pintype "passive"))
      (node (ref "D3") (pin "C") (pinfunction "C_C") (pintype "passive"))
    )
    (net (code "59") (name "Net-(D4-PadA)") (class "Default")
      (node (ref "D4") (pin "A") (pinfunction "A_A") (pintype "passive"))
      (node (ref "D5") (pin "C") (pinfunction "C_C") (pintype "passive"))
    )
    (net (code "60") (name "Net-(D5-PadA)") (class "Default")
      (node (ref "D5") (pin "A") (pinfunction "A_A") (pintype "passive"))
      (node (ref "D6") (pin "C") (pinfunction "C_C") (pintype "passive"))
    )
    (net (code "61") (name "Net-(D9-PadA)") (class "Default")
      (node (ref "D9") (pin "A") (pinfunction "A_A") (pintype "passive"))
      (node (ref "R12") (pin "1") (pinfunction "1_1") (pintype "passive"))
    )
    (net (code "62") (name "Net-(D10-C)") (class "Default")
      (node (ref "D10") (pin "K") (pinfunction "C_K") (pintype "passive"))
      (node (ref "K1") (pin "4") (pinfunction "K_4") (pintype "passive"))
      (node (ref "T1") (pin "C") (pinfunction "C_C") (pintype "passive"))
    )
    (net (code "63") (name "Net-(D10-PadA)") (class "Default")
      (node (ref "D10") (pin "A") (pinfunction "A_A") (pintype "passive"))
      (node (ref "R7") (pin "1") (pinfunction "1_1") (pintype "passive"))
    )
    (net (code "64") (name "Net-(D16-PadA)") (class "Default")
      (node (ref "D16") (pin "A") (pinfunction "A_A") (pintype "passive"))
      (node (ref "D17") (pin "C") (pinfunction "C_C") (pintype "passive"))
    )
    (net (code "65") (name "Net-(D17-PadA)") (class "Default")
      (node (ref "D17") (pin "A") (pinfunction "A_A") (pintype "passive"))
      (node (ref "D18") (pin "C") (pinfunction "C_C") (pintype "passive"))
    )
    (net (code "66") (name "Net-(D19-PadA)") (class "Default")
      (node (ref "D19") (pin "A") (pinfunction "A_A") (pintype "passive"))
      (node (ref "D20") (pin "C") (pinfunction "C_C") (pintype "passive"))
    )
    (net (code "67") (name "Net-(D20-PadA)") (class "Default")
      (node (ref "D20") (pin "A") (pinfunction "A_A") (pintype "passive"))
      (node (ref "D21") (pin "C") (pinfunction "C_C") (pintype "passive"))
    )
    (net (code "68") (name "Net-(D24-C)") (class "Default")
      (node (ref "D24") (pin "K") (pinfunction "C_K") (pintype "passive"))
      (node (ref "K2") (pin "4") (pinfunction "K_4") (pintype "passive"))
      (node (ref "T3") (pin "C") (pinfunction "C_C") (pintype "passive"))
    )
    (net (code "69") (name "Net-(D24-PadA)") (class "Default")
      (node (ref "D24") (pin "A") (pinfunction "A_A") (pintype "passive"))
      (node (ref "R22") (pin "1") (pinfunction "1_1") (pintype "passive"))
    )
    (net (code "70") (name "Net-(D25-PadA)") (class "Default")
      (node (ref "D25") (pin "A") (pinfunction "A_A") (pintype "passive"))
      (node (ref "D26") (pin "C") (pinfunction "C_C") (pintype "passive"))
    )
    (net (code "71") (name "Net-(D26-PadA)") (class "Default")
      (node (ref "D26") (pin "A") (pinfunction "A_A") (pintype "passive"))
      (node (ref "D27") (pin "C") (pinfunction "C_C") (pintype "passive"))
    )
    (net (code "72") (name "Net-(D28-PadA)") (class "Default")
      (node (ref "D28") (pin "A") (pinfunction "A_A") (pintype "passive"))
      (node (ref "D29") (pin "C") (pinfunction "C_C") (pintype "passive"))
    )
    (net (code "73") (name "Net-(D29-PadA)") (class "Default")
      (node (ref "D29") (pin "A") (pinfunction "A_A") (pintype "passive"))
      (node (ref "D30") (pin "C") (pinfunction "C_C") (pintype "passive"))
    )
    (net (code "74") (name "Net-(D33-C)") (class "Default")
      (node (ref "D33") (pin "K") (pinfunction "C_K") (pintype "passive"))
      (node (ref "K3") (pin "4") (pinfunction "K_4") (pintype "passive"))
      (node (ref "T4") (pin "C") (pinfunction "C_C") (pintype "passive"))
    )
    (net (code "75") (name "Net-(D33-PadA)") (class "Default")
      (node (ref "D33") (pin "A") (pinfunction "A_A") (pintype "passive"))
      (node (ref "R27") (pin "1") (pinfunction "1_1") (pintype "passive"))
    )
    (net (code "76") (name "Net-(D34-PadA)") (class "Default")
      (node (ref "D34") (pin "A") (pinfunction "A_A") (pintype "passive"))
      (node (ref "D35") (pin "C") (pinfunction "C_C") (pintype "passive"))
    )
    (net (code "77") (name "Net-(D35-PadA)") (class "Default")
      (node (ref "D35") (pin "A") (pinfunction "A_A") (pintype "passive"))
      (node (ref "D36") (pin "C") (pinfunction "C_C") (pintype "passive"))
    )
    (net (code "78") (name "Net-(D37-PadA)") (class "Default")
      (node (ref "D37") (pin "A") (pinfunction "A_A") (pintype "passive"))
      (node (ref "D38") (pin "C") (pinfunction "C_C") (pintype "passive"))
    )
    (net (code "79") (name "Net-(D38-PadA)") (class "Default")
      (node (ref "D38") (pin "A") (pinfunction "A_A") (pintype "passive"))
      (node (ref "D39") (pin "C") (pinfunction "C_C") (pintype "passive"))
    )
    (net (code "80") (name "Net-(D42-C)") (class "Default")
      (node (ref "D42") (pin "K") (pinfunction "C_K") (pintype "passive"))
      (node (ref "K4") (pin "4") (pinfunction "K_4") (pintype "passive"))
      (node (ref "T5") (pin "C") (pinfunction "C_C") (pintype "passive"))
    )
    (net (code "81") (name "Net-(D42-PadA)") (class "Default")
      (node (ref "D42") (pin "A") (pinfunction "A_A") (pintype "passive"))
      (node (ref "R32") (pin "1") (pinfunction "1_1") (pintype "passive"))
    )
    (net (code "82") (name "Net-(D43-PadA)") (class "Default")
      (node (ref "D43") (pin "A") (pinfunction "A_A") (pintype "passive"))
      (node (ref "D44") (pin "C") (pinfunction "C_C") (pintype "passive"))
    )
    (net (code "83") (name "Net-(D44-PadA)") (class "Default")
      (node (ref "D44") (pin "A") (pinfunction "A_A") (pintype "passive"))
      (node (ref "D45") (pin "C") (pinfunction "C_C") (pintype "passive"))
    )
    (net (code "84") (name "Net-(D46-PadA)") (class "Default")
      (node (ref "D46") (pin "A") (pinfunction "A_A") (pintype "passive"))
      (node (ref "D47") (pin "C") (pinfunction "C_C") (pintype "passive"))
    )
    (net (code "85") (name "Net-(D47-PadA)") (class "Default")
      (node (ref "D47") (pin "A") (pinfunction "A_A") (pintype "passive"))
      (node (ref "D48") (pin "C") (pinfunction "C_C") (pintype "passive"))
    )
    (net (code "86") (name "Net-(D51-C)") (class "Default")
      (node (ref "D51") (pin "K") (pinfunction "C_K") (pintype "passive"))
      (node (ref "K5") (pin "4") (pinfunction "K_4") (pintype "passive"))
      (node (ref "T6") (pin "C") (pinfunction "C_C") (pintype "passive"))
    )
    (net (code "87") (name "Net-(D51-PadA)") (class "Default")
      (node (ref "D51") (pin "A") (pinfunction "A_A") (pintype "passive"))
      (node (ref "R37") (pin "1") (pinfunction "1_1") (pintype "passive"))
    )
    (net (code "88") (name "Net-(D60-PadA)") (class "Default")
      (node (ref "D60") (pin "A") (pinfunction "A_A") (pintype "passive"))
      (node (ref "R42") (pin "1") (pinfunction "1_1") (pintype "passive"))
    )
    (net (code "89") (name "Net-(IC1-XTAL1)") (class "Default")
      (node (ref "C5") (pin "2") (pinfunction "2_2") (pintype "passive"))
      (node (ref "IC1") (pin "13") (pinfunction "XTAL1_13") (pintype "bidirectional"))
      (node (ref "Q1") (pin "1") (pinfunction "1_1") (pintype "passive"))
    )
    (net (code "90") (name "Net-(IC1-XTAL2)") (class "Default")
      (node (ref "C3") (pin "2") (pinfunction "2_2") (pintype "passive"))
      (node (ref "IC1") (pin "12") (pinfunction "XTAL2_12") (pintype "bidirectional"))
      (node (ref "Q1") (pin "2") (pinfunction "2_2") (pintype "passive"))
    )
    (net (code "91") (name "Net-(K1-DS2)") (class "Default")
      (node (ref "D3") (pin "A") (pinfunction "A_A") (pintype "passive"))
      (node (ref "D4") (pin "C") (pinfunction "C_C") (pintype "passive"))
      (node (ref "K1") (pin "2") (pinfunction "DS2_2") (pintype "passive"))
      (node (ref "OK1") (pin "2") (pinfunction "C_2") (pintype "passive"))
    )
    (net (code "92") (name "Net-(K2-DS2)") (class "Default")
      (node (ref "D18") (pin "A") (pinfunction "A_A") (pintype "passive"))
      (node (ref "D19") (pin "C") (pinfunction "C_C") (pintype "passive"))
      (node (ref "K2") (pin "2") (pinfunction "DS2_2") (pintype "passive"))
      (node (ref "OK3") (pin "2") (pinfunction "C_2") (pintype "passive"))
    )
    (net (code "93") (name "Net-(K3-DS2)") (class "Default")
      (node (ref "D27") (pin "A") (pinfunction "A_A") (pintype "passive"))
      (node (ref "D28") (pin "C") (pinfunction "C_C") (pintype "passive"))
      (node (ref "K3") (pin "2") (pinfunction "DS2_2") (pintype "passive"))
      (node (ref "OK4") (pin "2") (pinfunction "C_2") (pintype "passive"))
    )
    (net (code "94") (name "Net-(K4-DS2)") (class "Default")
      (node (ref "D36") (pin "A") (pinfunction "A_A") (pintype "passive"))
      (node (ref "D37") (pin "C") (pinfunction "C_C") (pintype "passive"))
      (node (ref "K4") (pin "2") (pinfunction "DS2_2") (pintype "passive"))
      (node (ref "OK5") (pin "2") (pinfunction "C_2") (pintype "passive"))
    )
    (net (code "95") (name "Net-(K5-DS2)") (class "Default")
      (node (ref "D45") (pin "A") (pinfunction "A_A") (pintype "passive"))
      (node (ref "D46") (pin "C") (pinfunction "C_C") (pintype "passive"))
      (node (ref "K5") (pin "2") (pinfunction "DS2_2") (pintype "passive"))
      (node (ref "OK6") (pin "2") (pinfunction "C_2") (pintype "passive"))
    )
    (net (code "96") (name "Net-(OK1-A)") (class "Default")
      (node (ref "OK1") (pin "1") (pinfunction "A_1") (pintype "passive"))
      (node (ref "R1") (pin "1") (pinfunction "1_1") (pintype "passive"))
    )
    (net (code "97") (name "Net-(OK1-COL)") (class "Default")
      (node (ref "C2") (pin "2") (pinfunction "2_2") (pintype "passive"))
      (node (ref "OK1") (pin "4") (pinfunction "COL_4") (pintype "passive"))
      (node (ref "R2") (pin "1") (pinfunction "1_1") (pintype "passive"))
    )
    (net (code "98") (name "Net-(OK2-A)") (class "Default")
      (node (ref "OK2") (pin "1") (pinfunction "A_1") (pintype "passive"))
      (node (ref "R18") (pin "1") (pinfunction "1_1") (pintype "passive"))
    )
    (net (code "99") (name "Net-(OK2-C)") (class "Default")
      (node (ref "OK2") (pin "2") (pinfunction "C_2") (pintype "passive"))
      (node (ref "T2") (pin "C") (pinfunction "C_C") (pintype "passive"))
    )
    (net (code "100") (name "Net-(OK3-A)") (class "Default")
      (node (ref "OK3") (pin "1") (pinfunction "A_1") (pintype "passive"))
      (node (ref "R20") (pin "1") (pinfunction "1_1") (pintype "passive"))
    )
    (net (code "101") (name "Net-(OK3-COL)") (class "Default")
      (node (ref "C13") (pin "2") (pinfunction "2_2") (pintype "passive"))
      (node (ref "OK3") (pin "4") (pinfunction "COL_4") (pintype "passive"))
      (node (ref "R21") (pin "1") (pinfunction "1_1") (pintype "passive"))
    )
    (net (code "102") (name "Net-(OK4-A)") (class "Default")
      (node (ref "OK4") (pin "1") (pinfunction "A_1") (pintype "passive"))
      (node (ref "R25") (pin "1") (pinfunction "1_1") (pintype "passive"))
    )
    (net (code "103") (name "Net-(OK4-COL)") (class "Default")
      (node (ref "C15") (pin "2") (pinfunction "2_2") (pintype "passive"))
      (node (ref "OK4") (pin "4") (pinfunction "COL_4") (pintype "passive"))
      (node (ref "R26") (pin "1") (pinfunction "1_1") (pintype "passive"))
    )
    (net (code "104") (name "Net-(OK5-A)") (class "Default")
      (node (ref "OK5") (pin "1") (pinfunction "A_1") (pintype "passive"))
      (node (ref "R30") (pin "1") (pinfunction "1_1") (pintype "passive"))
    )
    (net (code "105") (name "Net-(OK5-COL)") (class "Default")
      (node (ref "C17") (pin "2") (pinfunction "2_2") (pintype "passive"))
      (node (ref "OK5") (pin "4") (pinfunction "COL_4") (pintype "passive"))
      (node (ref "R31") (pin "1") (pinfunction "1_1") (pintype "passive"))
    )
    (net (code "106") (name "Net-(OK6-A)") (class "Default")
      (node (ref "OK6") (pin "1") (pinfunction "A_1") (pintype "passive"))
      (node (ref "R35") (pin "1") (pinfunction "1_1") (pintype "passive"))
    )
    (net (code "107") (name "Net-(OK6-COL)") (class "Default")
      (node (ref "C19") (pin "2") (pinfunction "2_2") (pintype "passive"))
      (node (ref "OK6") (pin "4") (pinfunction "COL_4") (pintype "passive"))
      (node (ref "R36") (pin "1") (pinfunction "1_1") (pintype "passive"))
    )
    (net (code "108") (name "Net-(R9-Pad2)") (class "Default")
      (node (ref "R9") (pin "2") (pinfunction "2_2") (pintype "passive"))
      (node (ref "T1") (pin "B") (pinfunction "B_B") (pintype "passive"))
    )
    (net (code "109") (name "Net-(R14-Pad2)") (class "Default")
      (node (ref "R14") (pin "2") (pinfunction "2_2") (pintype "passive"))
      (node (ref "SG1") (pin "-") (pinfunction "-_-") (pintype "passive"))
    )
    (net (code "110") (name "Net-(R23-Pad2)") (class "Default")
      (node (ref "R23") (pin "2") (pinfunction "2_2") (pintype "passive"))
      (node (ref "T3") (pin "B") (pinfunction "B_B") (pintype "passive"))
    )
    (net (code "111") (name "Net-(R28-Pad2)") (class "Default")
      (node (ref "R28") (pin "2") (pinfunction "2_2") (pintype "passive"))
      (node (ref "T4") (pin "B") (pinfunction "B_B") (pintype "passive"))
    )
    (net (code "112") (name "Net-(R33-Pad2)") (class "Default")
      (node (ref "R33") (pin "2") (pinfunction "2_2") (pintype "passive"))
      (node (ref "T5") (pin "B") (pinfunction "B_B") (pintype "passive"))
    )
    (net (code "113") (name "Net-(R38-Pad2)") (class "Default")
      (node (ref "R38") (pin "2") (pinfunction "2_2") (pintype "passive"))
      (node (ref "T6") (pin "B") (pinfunction "B_B") (pintype "passive"))
    )
    (net (code "114") (name "Net-(U$1-FILT)") (class "Default")
      (node (ref "C31") (pin "1") (pinfunction "1_1") (pintype "passive"))
      (node (ref "U$1") (pin "6") (pinfunction "FILT_6") (pintype "bidirectional"))
    )
    (net (code "115") (name "OK") (class "Default")
      (node (ref "IC1") (pin "39") (pinfunction "(ADC1)PA1_39") (pintype "bidirectional"))
      (node (ref "X13") (pin "2") (pinfunction "KL_2") (pintype "passive"))
    )
    (net (code "116") (name "OUT_PUMP") (class "Default")
      (node (ref "K5") (pin "1") (pinfunction "DS1_1") (pintype "passive"))
      (node (ref "X6") (pin "1") (pinfunction "KL_1") (pintype "passive"))
    )
    (net (code "117") (name "OUT_S1_GAS") (class "Default")
      (node (ref "K4") (pin "1") (pinfunction "DS1_1") (pintype "passive"))
      (node (ref "X2") (pin "1") (pinfunction "KL_1") (pintype "passive"))
    )
    (net (code "118") (name "OUT_S2_WAT") (class "Default")
      (node (ref "K3") (pin "1") (pinfunction "DS1_1") (pintype "passive"))
      (node (ref "X3") (pin "1") (pinfunction "KL_1") (pintype "passive"))
    )
    (net (code "119") (name "OUT_S3_VAP") (class "Default")
      (node (ref "K2") (pin "1") (pinfunction "DS1_1") (pintype "passive"))
      (node (ref "X4") (pin "1") (pinfunction "KL_1") (pintype "passive"))
    )
    (net (code "120") (name "OUT_S4_DRY") (class "Default")
      (node (ref "K1") (pin "1") (pinfunction "DS1_1") (pintype "passive"))
      (node (ref "X5") (pin "1") (pinfunction "KL_1") (pintype "passive"))
    )
    (net (code "121") (name "PRES_SEN") (class "Default")
      (node (ref "IC1") (pin "6") (pinfunction "(MOSI)PB5_6") (pintype "bidirectional"))
      (node (ref "X10") (pin "1") (pinfunction "KL_1") (pintype "passive"))
    )
    (net (code "122") (name "PUMP_FED_SIG") (class "Default")
      (node (ref "C36") (pin "1") (pinfunction "1_1") (pintype "passive"))
      (node (ref "D49") (pin "C") (pinfunction "C_C") (pintype "passive"))
      (node (ref "IC1") (pin "29") (pinfunction "(TOSC2)PC7_29") (pintype "bidirectional"))
      (node (ref "R39") (pin "2") (pinfunction "2_2") (pintype "passive"))
    )
    (net (code "123") (name "REST") (class "Default")
      (node (ref "IC1") (pin "9") (pinfunction "RESET_9") (pintype "input"))
      (node (ref "JP1") (pin "2") (pinfunction "2_2") (pintype "passive"))
      (node (ref "R8") (pin "1") (pinfunction "1_1") (pintype "passive"))
    )
    (net (code "124") (name "REST_OUT") (class "Default")
      (node (ref "JP1") (pin "1") (pinfunction "1_1") (pintype "passive"))
      (node (ref "SJR1") (pin "13") (pinfunction "GPIO4_13") (pintype "bidirectional"))
    )
    (net (code "125") (name "RS") (class "Default")
      (node (ref "J1") (pin "4") (pinfunction "4_4") (pintype "passive"))
      (node (ref "V1") (pin "7") (pinfunction "QH_7") (pintype "tri_state"))
    )
    (net (code "126") (name "S1_GAS_FED_SIG") (class "Default")
      (node (ref "C35") (pin "1") (pinfunction "1_1") (pintype "passive"))
      (node (ref "D40") (pin "C") (pinfunction "C_C") (pintype "passive"))
      (node (ref "IC1") (pin "35") (pinfunction "(ADC5)PA5_35") (pintype "bidirectional"))
      (node (ref "R34") (pin "2") (pinfunction "2_2") (pintype "passive"))
    )
    (net (code "127") (name "S2_WAT_FED_SIG") (class "Default")
      (node (ref "C34") (pin "1") (pinfunction "1_1") (pintype "passive"))
      (node (ref "D31") (pin "C") (pinfunction "C_C") (pintype "passive"))
      (node (ref "IC1") (pin "27") (pinfunction "(TDI)PC5_27") (pintype "bidirectional"))
      (node (ref "R29") (pin "2") (pinfunction "2_2") (pintype "passive"))
    )
    (net (code "128") (name "S3_VAP_FED_SIG") (class "Default")
      (node (ref "C33") (pin "1") (pinfunction "1_1") (pintype "passive"))
      (node (ref "D22") (pin "C") (pinfunction "C_C") (pintype "passive"))
      (node (ref "IC1") (pin "23") (pinfunction "(SDA)PC1_23") (pintype "bidirectional"))
      (node (ref "R24") (pin "2") (pinfunction "2_2") (pintype "passive"))
    )
    (net (code "129") (name "S4_DRY_FED_SIG") (class "Default")
      (node (ref "C32") (pin "1") (pinfunction "1_1") (pintype "passive"))
      (node (ref "D7") (pin "C") (pinfunction "C_C") (pintype "passive"))
      (node (ref "IC1") (pin "21") (pinfunction "(OC2)PD7_21") (pintype "bidirectional"))
      (node (ref "R13") (pin "2") (pinfunction "2_2") (pintype "passive"))
    )
    (net (code "130") (name "SCL3") (class "Default")
      (node (ref "SJR1") (pin "14") (pinfunction "GPIO5_14") (pintype "bidirectional"))
    )
    (net (code "131") (name "TCK+") (class "Default")
      (node (ref "U1") (pin "3") (pinfunction "T+_3") (pintype "bidirectional"))
      (node (ref "X15") (pin "2") (pinfunction "KL_2") (pintype "passive"))
    )
    (net (code "132") (name "TCK-") (class "Default")
      (node (ref "U1") (pin "2") (pinfunction "T-_2") (pintype "bidirectional"))
      (node (ref "X15") (pin "1") (pinfunction "KL_1") (pintype "passive"))
    )
    (net (code "133") (name "T_CLK") (class "Default")
      (node (ref "IC1") (pin "3") (pinfunction "(AIN0/INT2)PB2_3") (pintype "bidirectional"))
      (node (ref "U1") (pin "6") (pinfunction "~{CS}_6") (pintype "bidirectional"))
    )
    (net (code "134") (name "T_CS") (class "Default")
      (node (ref "IC1") (pin "2") (pinfunction "(T1)PB1_2") (pintype "bidirectional"))
      (node (ref "U1") (pin "5") (pinfunction "SCK_5") (pintype "bidirectional"))
    )
    (net (code "135") (name "T_DO") (class "Default")
      (node (ref "IC1") (pin "4") (pinfunction "(AIN1/OC0)PB3_4") (pintype "bidirectional"))
      (node (ref "U1") (pin "7") (pinfunction "(MI)SO_7") (pintype "bidirectional"))
    )
    (net (code "136") (name "UP") (class "Default")
      (node (ref "IC1") (pin "38") (pinfunction "(ADC2)PA2_38") (pintype "bidirectional"))
      (node (ref "X13") (pin "1") (pinfunction "KL_1") (pintype "passive"))
    )
    (net (code "137") (name "VEE") (class "Default")
      (node (ref "C11") (pin "2") (pinfunction "2_2") (pintype "passive"))
      (node (ref "C4") (pin "+") (pinfunction "+_+") (pintype "passive"))
      (node (ref "J1") (pin "3") (pinfunction "3_3") (pintype "passive"))
      (node (ref "R11") (pin "1") (pinfunction "1_1") (pintype "passive"))
    )
    (net (code "138") (name "VIN") (class "Default")
      (node (ref "B2") (pin "+") (pinfunction "+_+") (pintype "passive"))
      (node (ref "C22") (pin "+") (pinfunction "+_+") (pintype "passive"))
      (node (ref "C23") (pin "2") (pinfunction "2_2") (pintype "passive"))
      (node (ref "IC2") (pin "IN") (pinfunction "IN_IN") (pintype "input"))
      (node (ref "IC4") (pin "IN") (pinfunction "IN_IN") (pintype "input"))
      (node (ref "R42") (pin "2") (pinfunction "2_2") (pintype "passive"))
    )
    (net (code "139") (name "WATER_SEN") (class "Default")
      (node (ref "IC1") (pin "5") (pinfunction "(SS)PB4_5") (pintype "bidirectional"))
      (node (ref "X9") (pin "1") (pinfunction "KL_1") (pintype "passive"))
    )
    (net (code "140") (name "ZERO_CROSS") (class "Default")
      (node (ref "IC1") (pin "16") (pinfunction "(INT0)PD2_16") (pintype "bidirectional"))
      (node (ref "OK2") (pin "5") (pinfunction "COL_5") (pintype "passive"))
      (node (ref "R19") (pin "2") (pinfunction "2_2") (pintype "passive"))
    )
    (net (code "141") (name "unconnected-(IC1-(ADC6)PA6-Pad34)") (class "Default")
      (node (ref "IC1") (pin "34") (pinfunction "(ADC6)PA6_34") (pintype "bidirectional"))
    )
    (net (code "142") (name "unconnected-(IC1-AREF-Pad32)") (class "Default")
      (node (ref "IC1") (pin "32") (pinfunction "AREF_32") (pintype "passive"))
    )
    (net (code "143") (name "unconnected-(OK2-BAS-Pad6)") (class "Default")
      (node (ref "OK2") (pin "6") (pinfunction "BAS_6") (pintype "passive"))
    )
    (net (code "144") (name "unconnected-(SJR1-CS0-Pad17)") (class "Default")
      (node (ref "SJR1") (pin "17") (pinfunction "CS0_17") (pintype "bidirectional"))
    )
    (net (code "145") (name "unconnected-(SJR1-GPIO9-Pad19)") (class "Default")
      (node (ref "SJR1") (pin "19") (pinfunction "GPIO9_19") (pintype "bidirectional"))
    )
    (net (code "146") (name "unconnected-(SJR1-GPIO10-Pad20)") (class "Default")
      (node (ref "SJR1") (pin "20") (pinfunction "GPIO10_20") (pintype "bidirectional"))
    )
    (net (code "147") (name "unconnected-(SJR1-MISO-Pad18)") (class "Default")
      (node (ref "SJR1") (pin "18") (pinfunction "MISO_18") (pintype "bidirectional"))
    )
    (net (code "148") (name "unconnected-(SJR1-MOSI-Pad21)") (class "Default")
      (node (ref "SJR1") (pin "21") (pinfunction "MOSI_21") (pintype "bidirectional"))
    )
    (net (code "149") (name "unconnected-(SJR1-SCLK-Pad22)") (class "Default")
      (node (ref "SJR1") (pin "22") (pinfunction "SCLK_22") (pintype "bidirectional"))
    )
    (net (code "150") (name "unconnected-(V1C-QE-Pad4)") (class "Default")
      (node (ref "V1") (pin "4") (pinfunction "QE_4") (pintype "tri_state"))
    )
    (net (code "151") (name "unconnected-(V1C-QF-Pad5)") (class "Default")
      (node (ref "V1") (pin "5") (pinfunction "QF_5") (pintype "tri_state"))
    )
    (net (code "152") (name "unconnected-(V1C-QH*-Pad9)") (class "Default")
      (node (ref "V1") (pin "9") (pinfunction "QH*_9") (pintype "output"))
    )
  )
)
